# umotion_2_v1_2_pcb_2.net
KiCad netlist of a schematic drawn in EAGLE
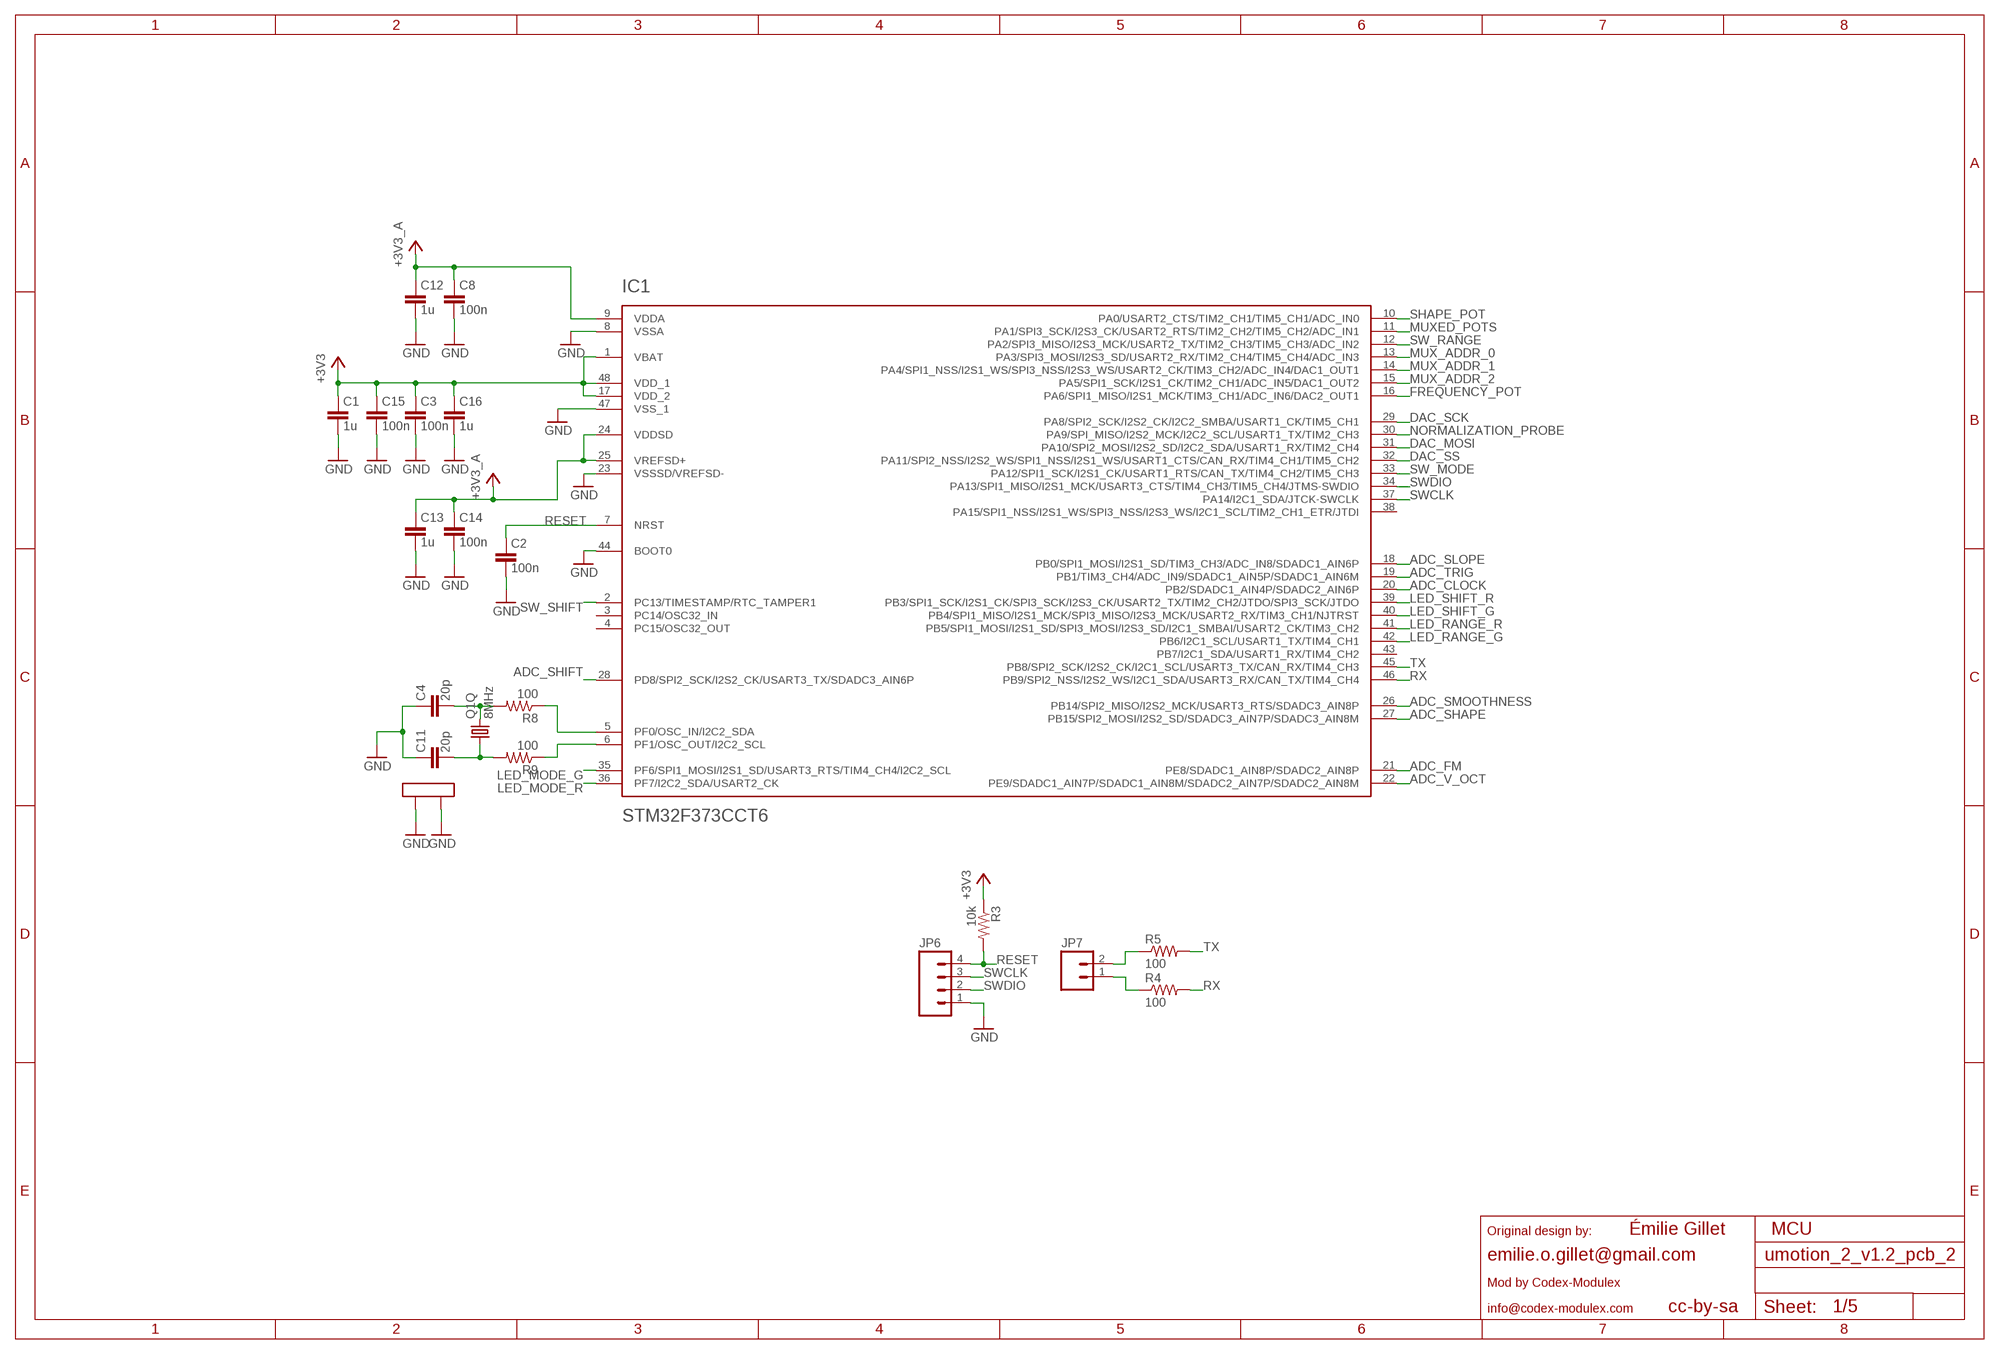
[diagram p0: schematic, sheet 1]
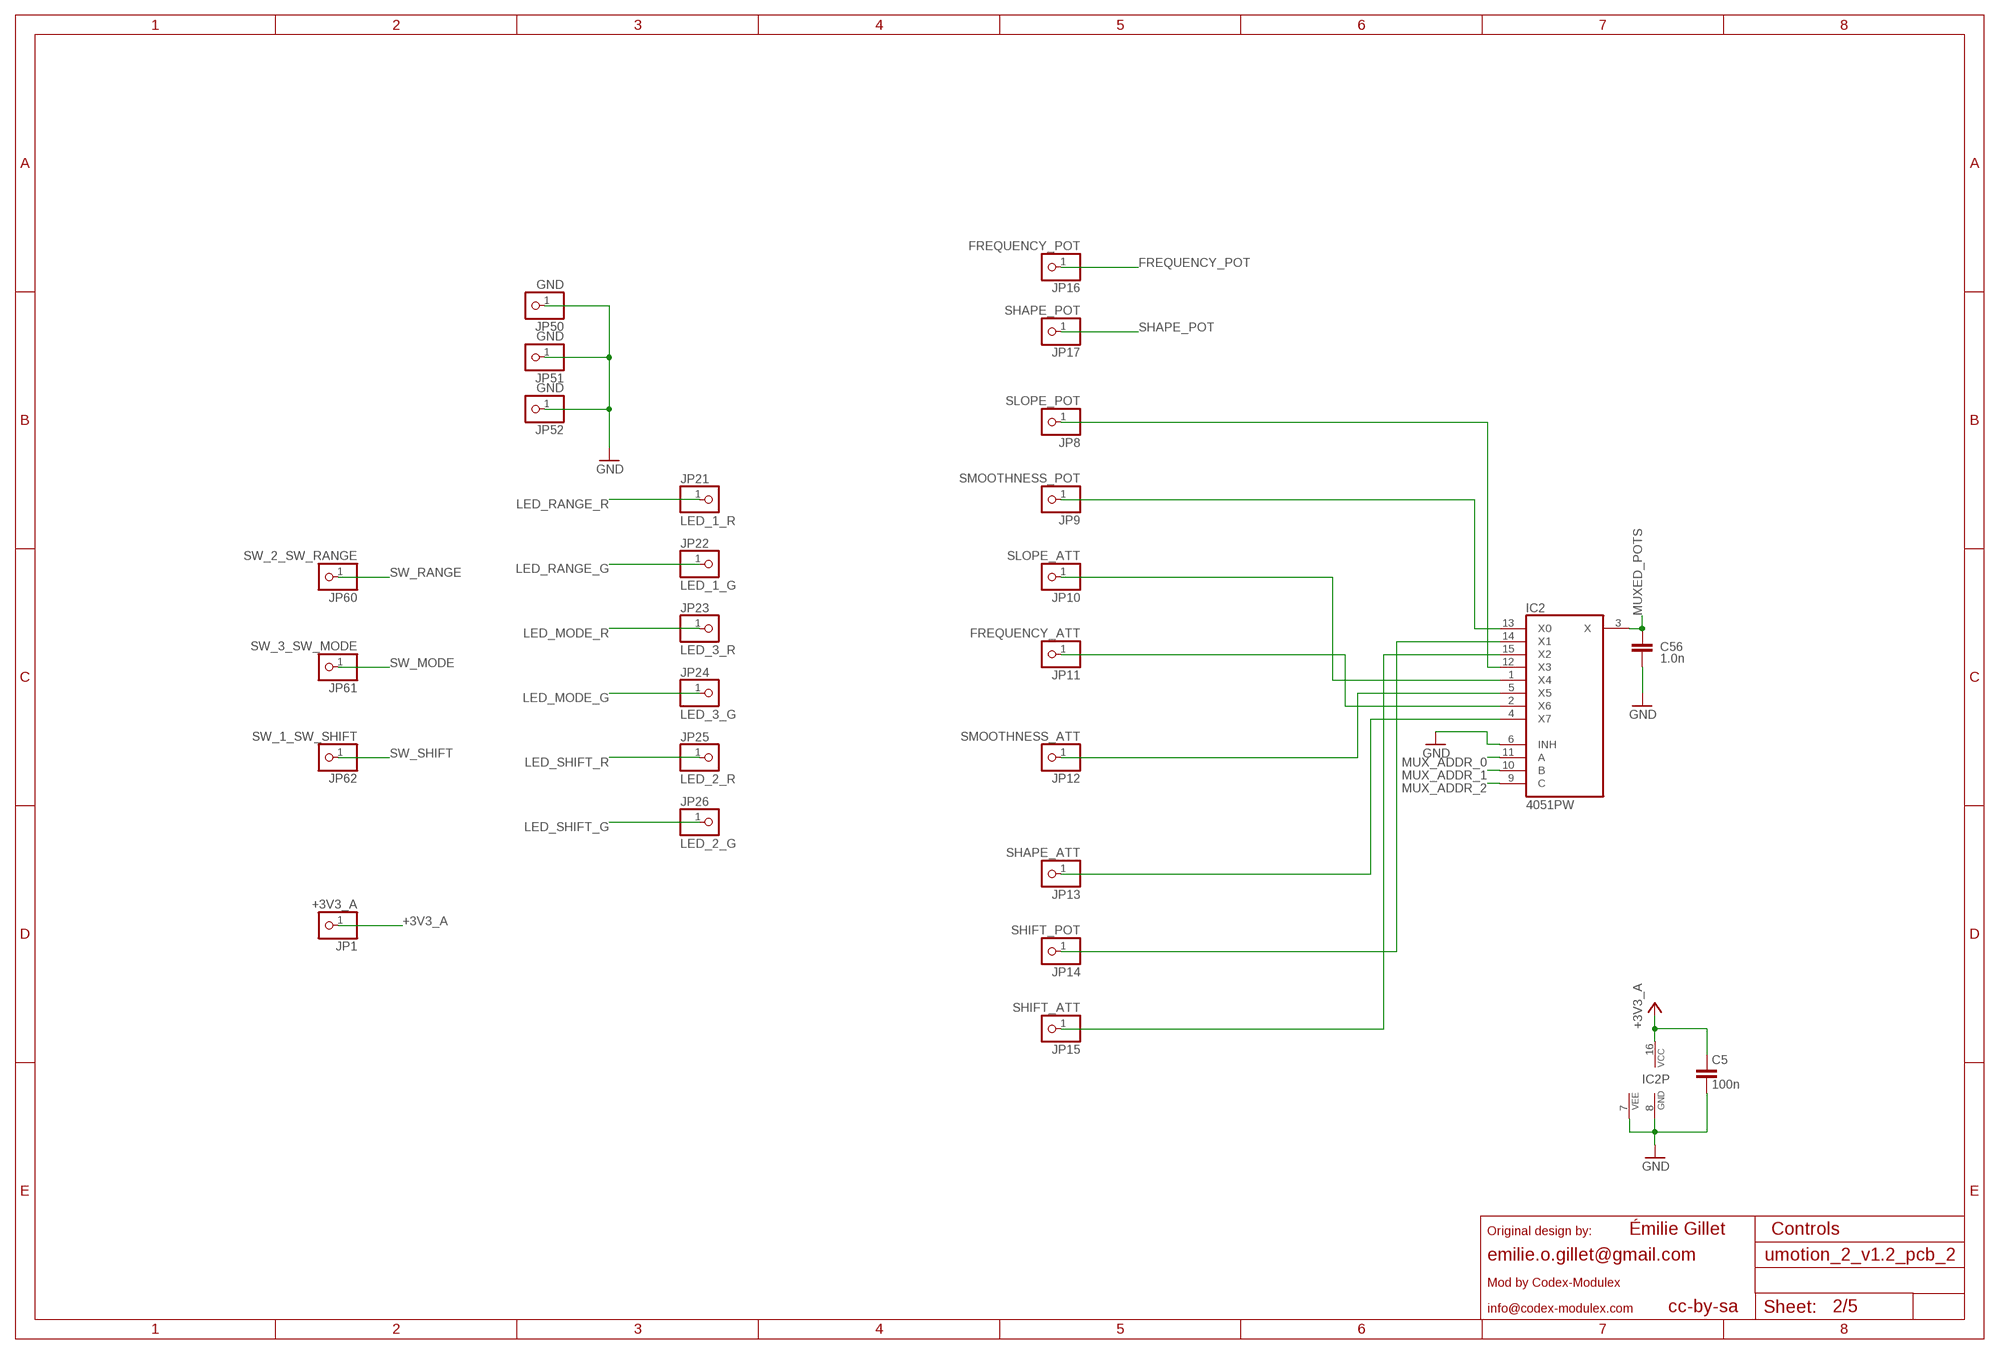
[diagram p1: schematic, sheet 2]
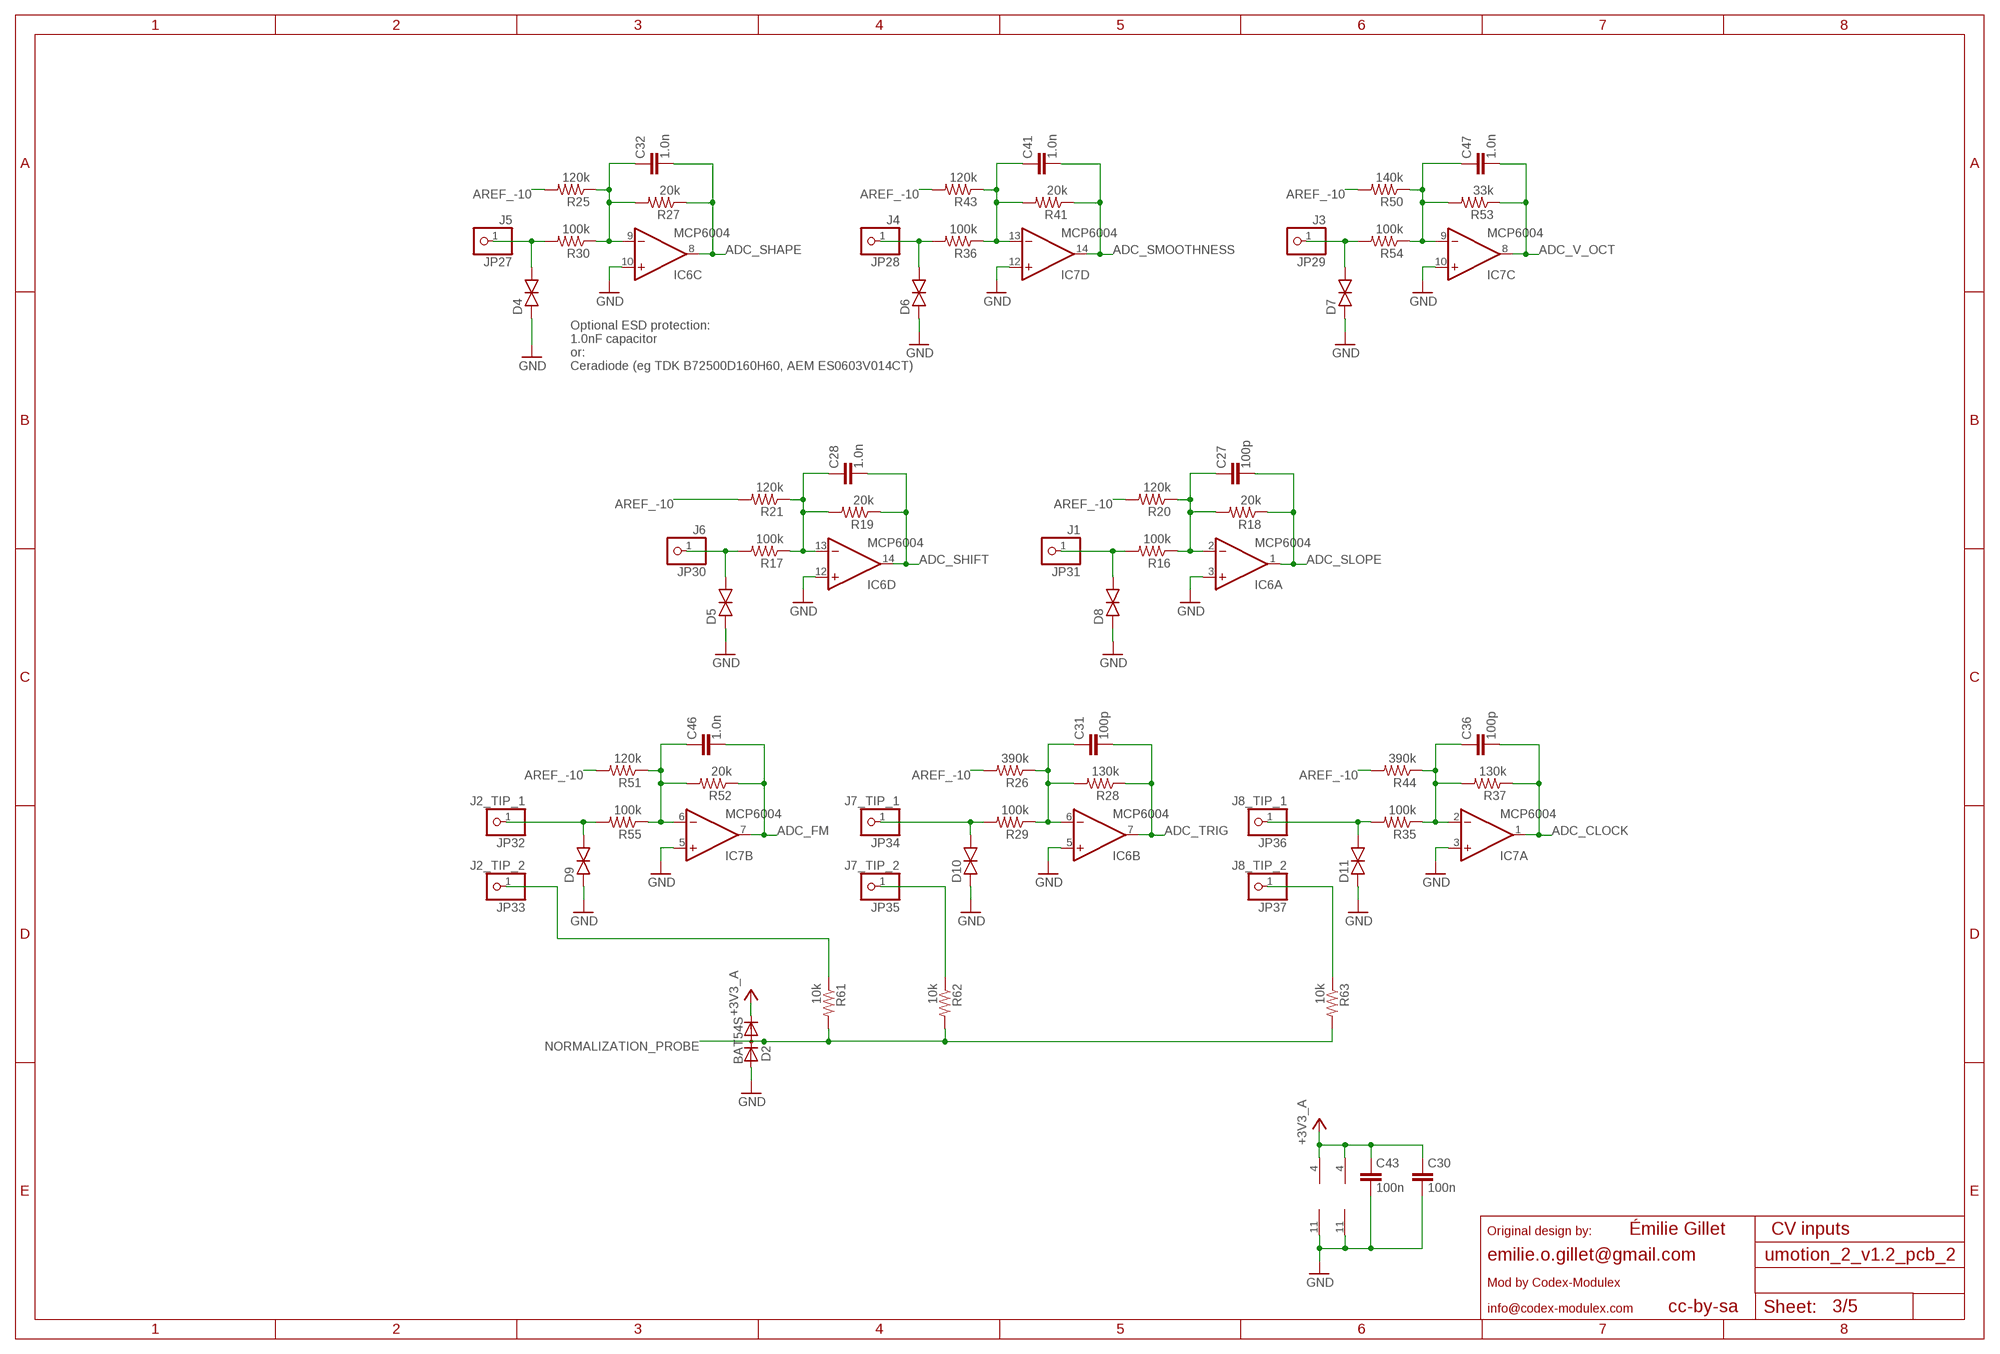
[diagram p2: schematic, sheet 3]
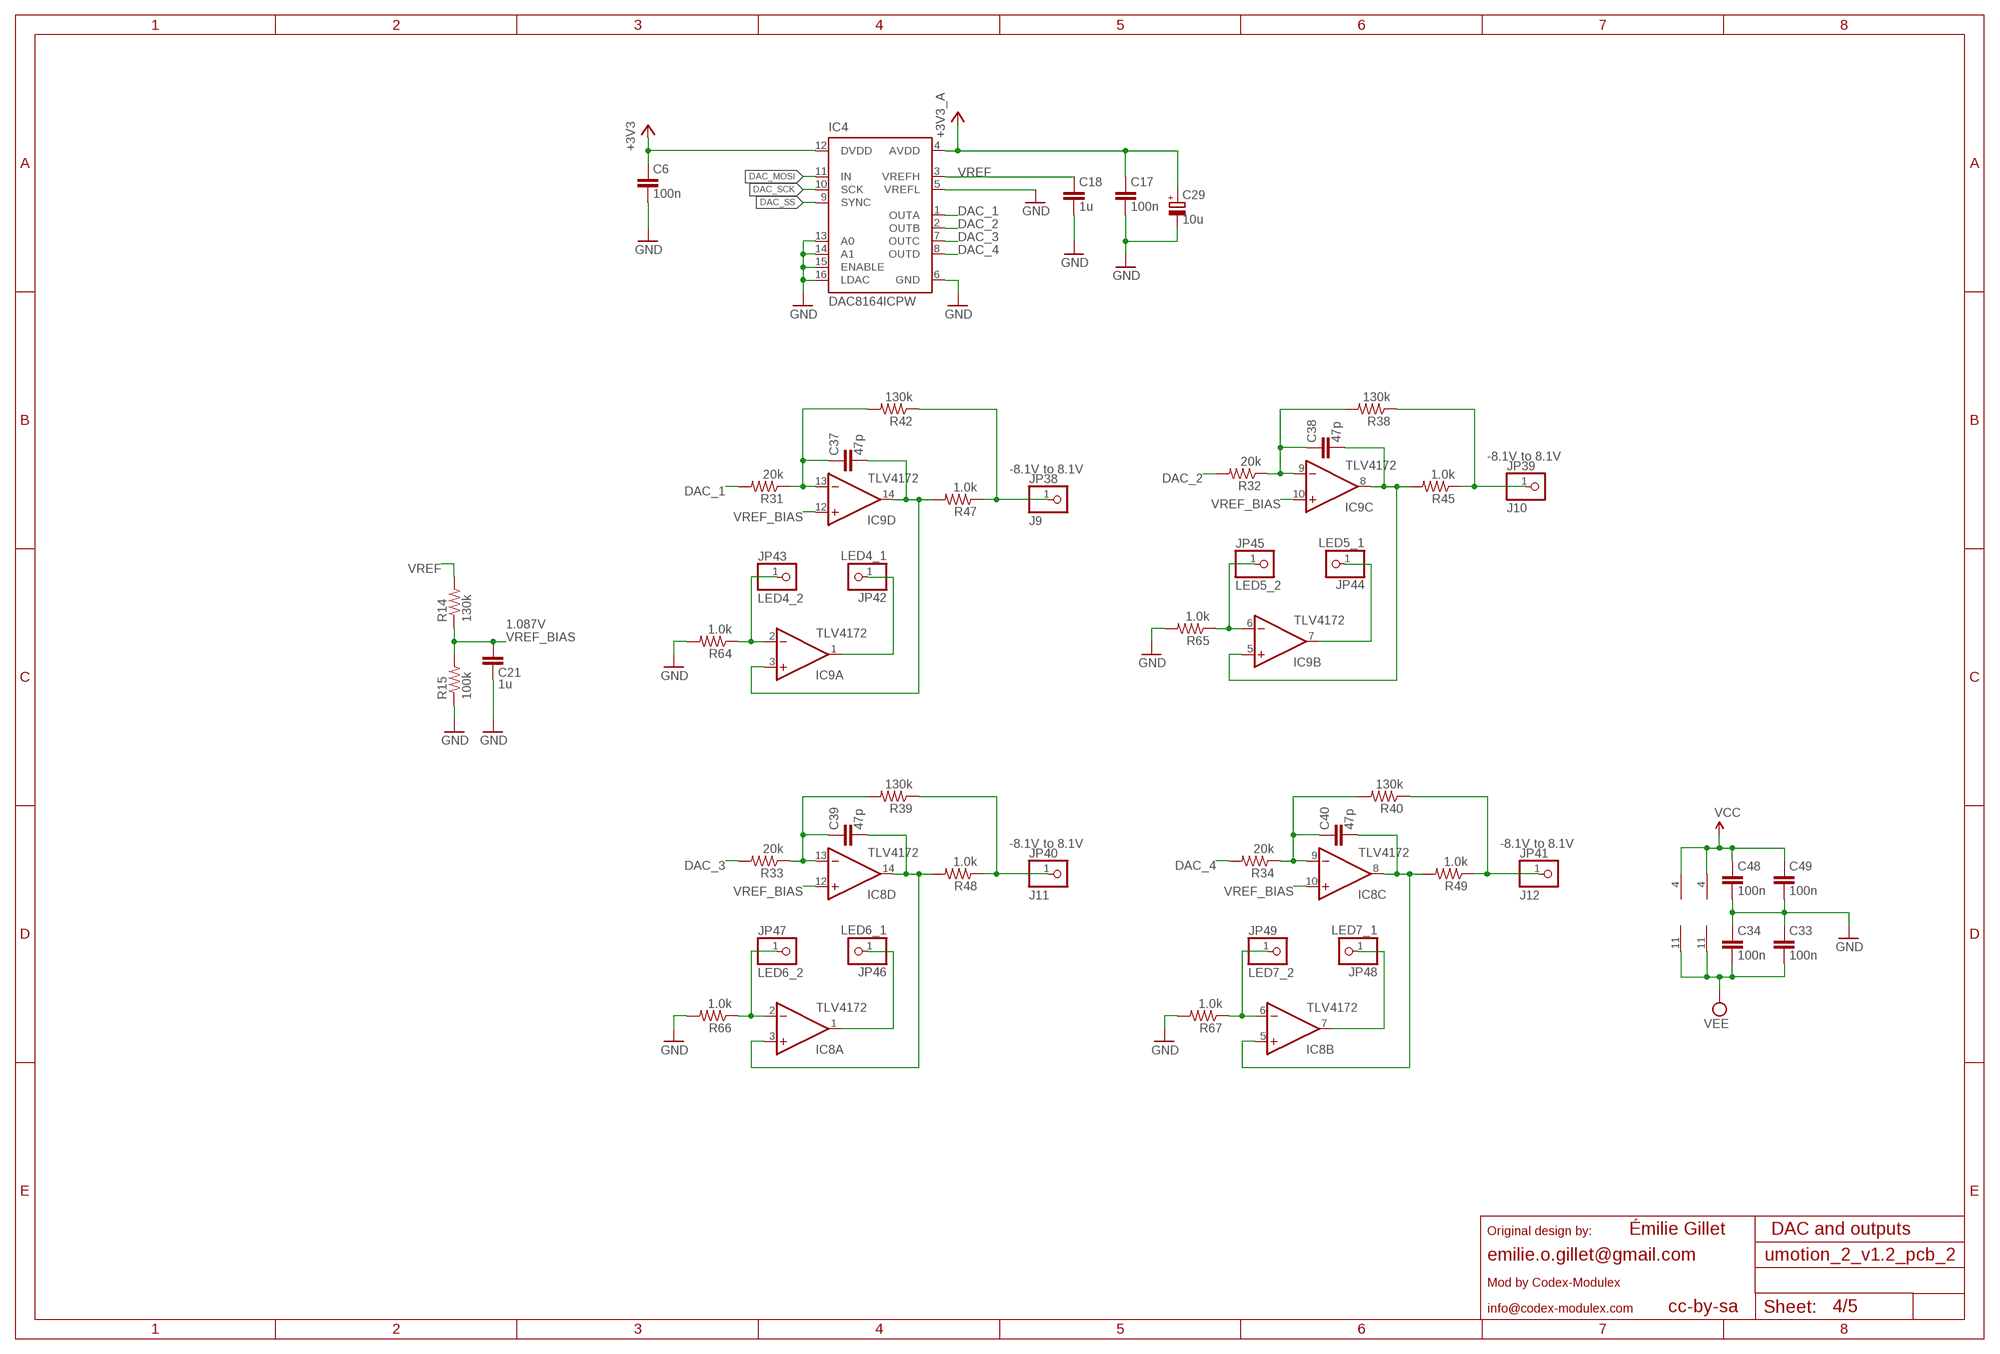
[diagram p3: schematic, sheet 4]
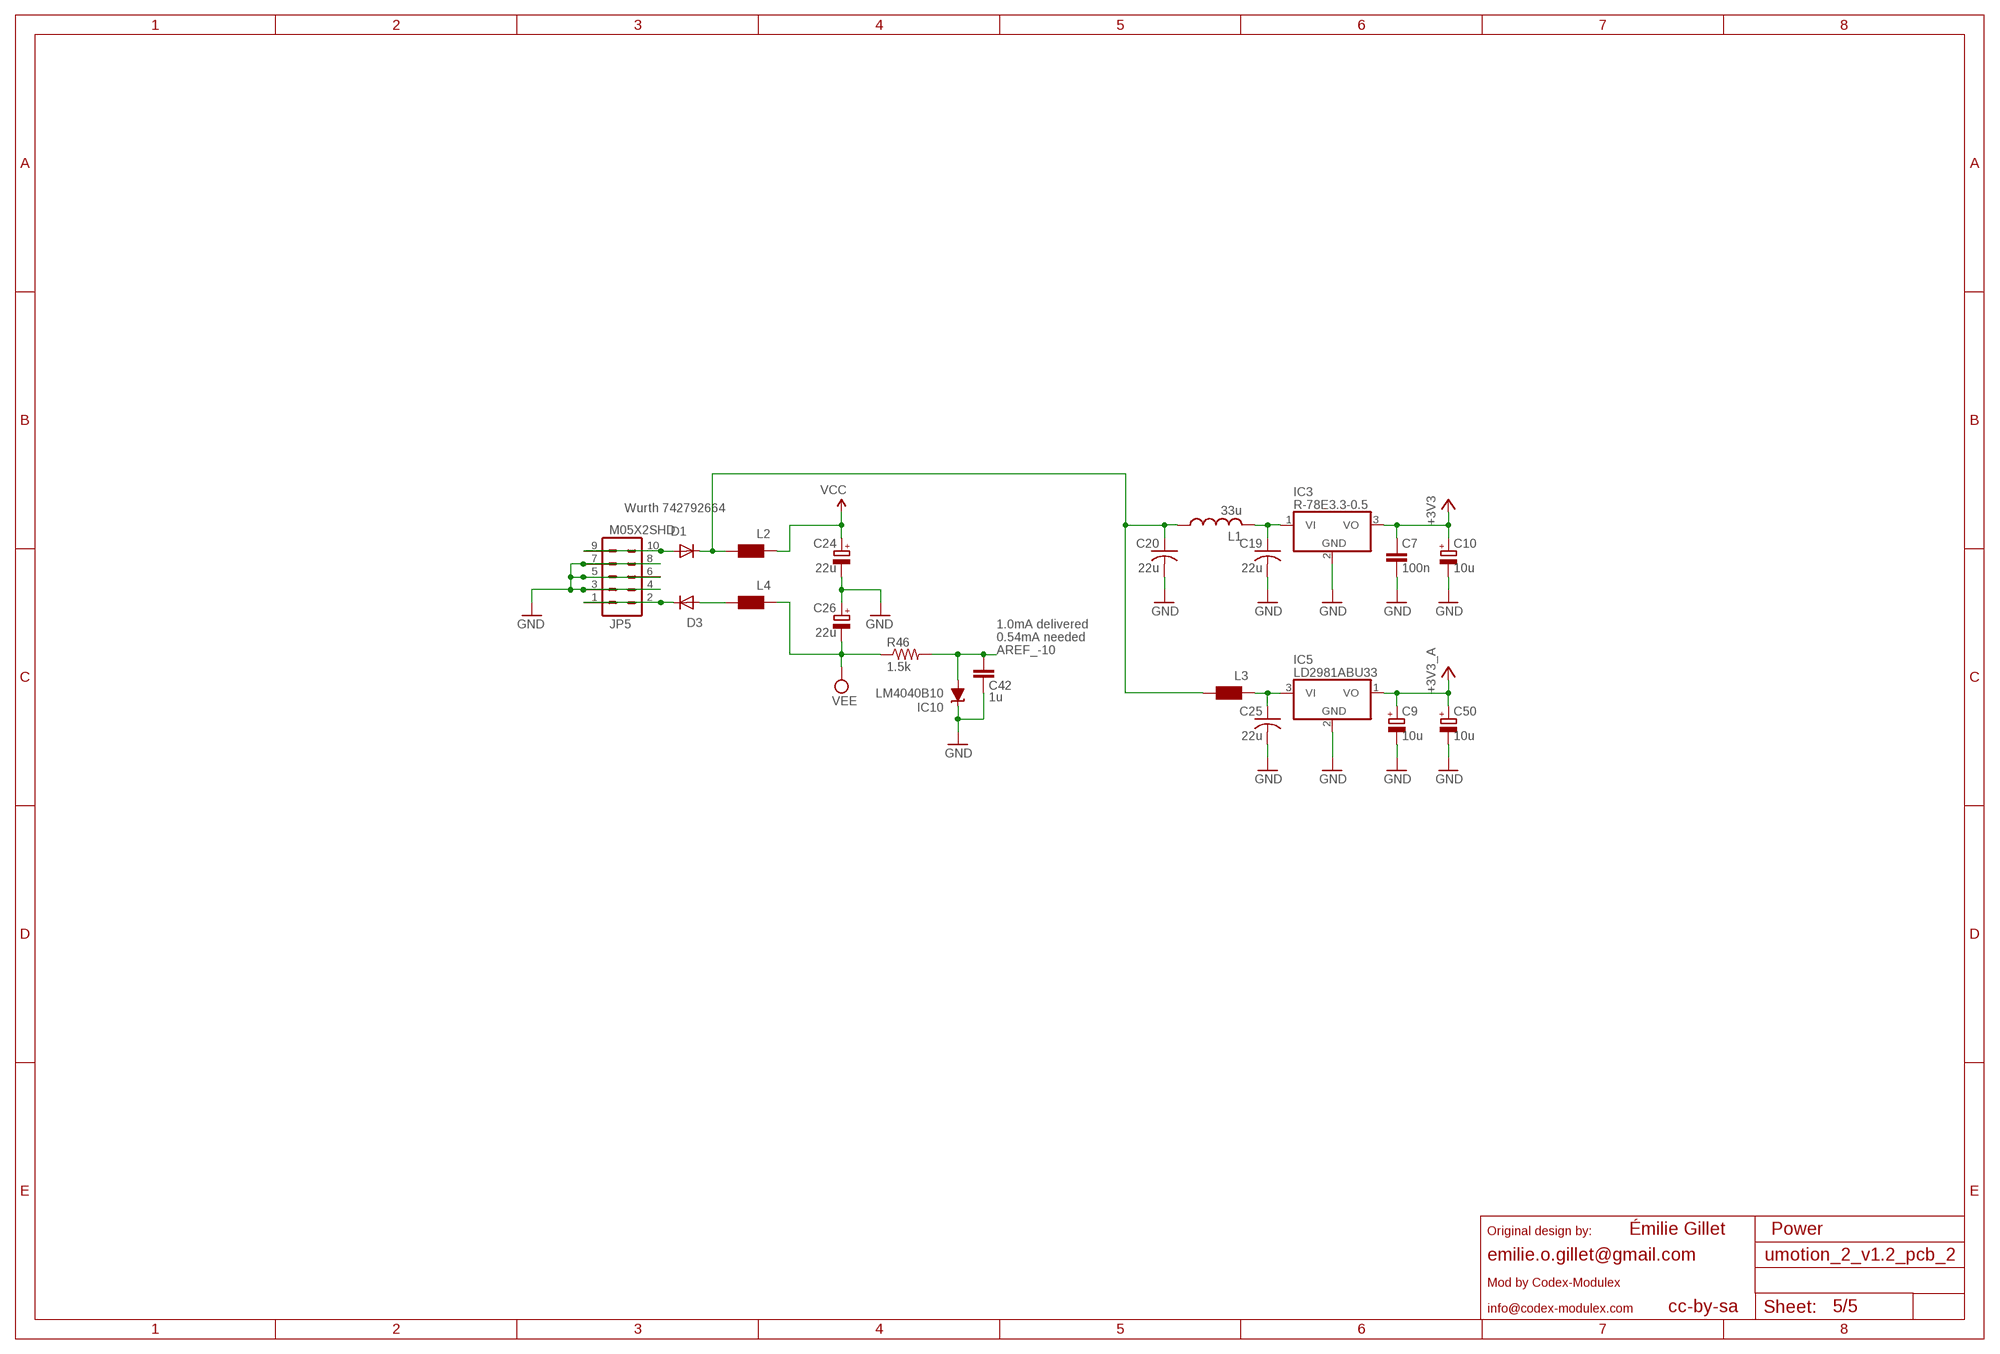
[diagram p4: schematic, sheet 5]

(export (version "E")
  (design (tool "Eeschema 10.0.6"))
  (components
    (comp (ref "C6")
      (value "100n")
      (footprint "eagle-import:PARTS_AMAN_RESISTOR_0603")
      (libsource (lib "eagle-import") (part "PARTS_AMAN_CAPACITOR"))
    )
    (comp (ref "C17")
      (value "100n")
      (footprint "eagle-import:PARTS_AMAN_RESISTOR_0603")
      (libsource (lib "eagle-import") (part "PARTS_AMAN_CAPACITOR"))
    )
    (comp (ref "C18")
      (value "1u")
      (footprint "eagle-import:PARTS_AMAN_RESISTOR_0603")
      (libsource (lib "eagle-import") (part "PARTS_AMAN_CAPACITOR"))
    )
    (comp (ref "C21")
      (value "1u")
      (footprint "eagle-import:PARTS_AMAN_RESISTOR_0603")
      (libsource (lib "eagle-import") (part "PARTS_AMAN_CAPACITOR"))
    )
    (comp (ref "C29")
      (value "10u")
      (footprint "eagle-import:PANASONIC_B")
      (libsource (lib "eagle-import") (part "CPOL-EUB"))
    )
    (comp (ref "C33")
      (value "100n")
      (footprint "eagle-import:PARTS_AMAN_RESISTOR_0603")
      (libsource (lib "eagle-import") (part "PARTS_AMAN_CAPACITOR"))
    )
    (comp (ref "C34")
      (value "100n")
      (footprint "eagle-import:PARTS_AMAN_RESISTOR_0603")
      (libsource (lib "eagle-import") (part "PARTS_AMAN_CAPACITOR"))
    )
    (comp (ref "C37")
      (value "47p")
      (footprint "eagle-import:PARTS_AMAN_RESISTOR_0603")
      (libsource (lib "eagle-import") (part "PARTS_AMAN_CAPACITOR"))
    )
    (comp (ref "C38")
      (value "47p")
      (footprint "eagle-import:PARTS_AMAN_RESISTOR_0603")
      (libsource (lib "eagle-import") (part "PARTS_AMAN_CAPACITOR"))
    )
    (comp (ref "C39")
      (value "47p")
      (footprint "eagle-import:PARTS_AMAN_RESISTOR_0603")
      (libsource (lib "eagle-import") (part "PARTS_AMAN_CAPACITOR"))
    )
    (comp (ref "C40")
      (value "47p")
      (footprint "eagle-import:PARTS_AMAN_RESISTOR_0603")
      (libsource (lib "eagle-import") (part "PARTS_AMAN_CAPACITOR"))
    )
    (comp (ref "C48")
      (value "100n")
      (footprint "eagle-import:PARTS_AMAN_RESISTOR_0603")
      (libsource (lib "eagle-import") (part "PARTS_AMAN_CAPACITOR"))
    )
    (comp (ref "C49")
      (value "100n")
      (footprint "eagle-import:PARTS_AMAN_RESISTOR_0603")
      (libsource (lib "eagle-import") (part "PARTS_AMAN_CAPACITOR"))
    )
    (comp (ref "IC4")
      (value "DAC8164ICPW")
      (footprint "eagle-import:SOP65P640X110-16N")
      (libsource (lib "eagle-import") (part "DAC8564"))
    )
    (comp (ref "IC8")
      (value "TLV4172")
      (footprint "eagle-import:TSSOP14_065")
      (libsource (lib "eagle-import") (part "TL074PW"))
    )
    (comp (ref "IC9")
      (value "TLV4172")
      (footprint "eagle-import:TSSOP14_065")
      (libsource (lib "eagle-import") (part "TL074PW"))
    )
    (comp (ref "JP38")
      (value "J9")
      (footprint "eagle-import:PARTS_AMAN_1X01")
      (libsource (lib "eagle-import") (part "PARTS_AMAN_PINHD-1X1"))
    )
    (comp (ref "JP39")
      (value "J10")
      (footprint "eagle-import:PARTS_AMAN_1X01")
      (libsource (lib "eagle-import") (part "PARTS_AMAN_PINHD-1X1"))
    )
    (comp (ref "JP40")
      (value "J11")
      (footprint "eagle-import:PARTS_AMAN_1X01")
      (libsource (lib "eagle-import") (part "PARTS_AMAN_PINHD-1X1"))
    )
    (comp (ref "JP41")
      (value "J12")
      (footprint "eagle-import:PARTS_AMAN_1X01")
      (libsource (lib "eagle-import") (part "PARTS_AMAN_PINHD-1X1"))
    )
    (comp (ref "JP42")
      (value "LED4_1")
      (footprint "eagle-import:PARTS_AMAN_1X01")
      (libsource (lib "eagle-import") (part "PARTS_AMAN_PINHD-1X1"))
    )
    (comp (ref "JP43")
      (value "LED4_2")
      (footprint "eagle-import:PARTS_AMAN_1X01")
      (libsource (lib "eagle-import") (part "PARTS_AMAN_PINHD-1X1"))
    )
    (comp (ref "JP44")
      (value "LED5_1")
      (footprint "eagle-import:PARTS_AMAN_1X01")
      (libsource (lib "eagle-import") (part "PARTS_AMAN_PINHD-1X1"))
    )
    (comp (ref "JP45")
      (value "LED5_2")
      (footprint "eagle-import:PARTS_AMAN_1X01")
      (libsource (lib "eagle-import") (part "PARTS_AMAN_PINHD-1X1"))
    )
    (comp (ref "JP46")
      (value "LED6_1")
      (footprint "eagle-import:PARTS_AMAN_1X01")
      (libsource (lib "eagle-import") (part "PARTS_AMAN_PINHD-1X1"))
    )
    (comp (ref "JP47")
      (value "LED6_2")
      (footprint "eagle-import:PARTS_AMAN_1X01")
      (libsource (lib "eagle-import") (part "PARTS_AMAN_PINHD-1X1"))
    )
    (comp (ref "JP48")
      (value "LED7_1")
      (footprint "eagle-import:PARTS_AMAN_1X01")
      (libsource (lib "eagle-import") (part "PARTS_AMAN_PINHD-1X1"))
    )
    (comp (ref "JP49")
      (value "LED7_2")
      (footprint "eagle-import:PARTS_AMAN_1X01")
      (libsource (lib "eagle-import") (part "PARTS_AMAN_PINHD-1X1"))
    )
    (comp (ref "R14")
      (value "130k")
      (footprint "eagle-import:PARTS_AMAN_RESISTOR_0603")
      (libsource (lib "eagle-import") (part "PARTS_AMAN_RESISTOR"))
    )
    (comp (ref "R15")
      (value "100k")
      (footprint "eagle-import:PARTS_AMAN_RESISTOR_0603")
      (libsource (lib "eagle-import") (part "PARTS_AMAN_RESISTOR"))
    )
    (comp (ref "R31")
      (value "20k")
      (footprint "eagle-import:PARTS_AMAN_RESISTOR_0603")
      (libsource (lib "eagle-import") (part "PARTS_AMAN_RESISTOR"))
    )
    (comp (ref "R32")
      (value "20k")
      (footprint "eagle-import:PARTS_AMAN_RESISTOR_0603")
      (libsource (lib "eagle-import") (part "PARTS_AMAN_RESISTOR"))
    )
    (comp (ref "R33")
      (value "20k")
      (footprint "eagle-import:PARTS_AMAN_RESISTOR_0603")
      (libsource (lib "eagle-import") (part "PARTS_AMAN_RESISTOR"))
    )
    (comp (ref "R34")
      (value "20k")
      (footprint "eagle-import:PARTS_AMAN_RESISTOR_0603")
      (libsource (lib "eagle-import") (part "PARTS_AMAN_RESISTOR"))
    )
    (comp (ref "R38")
      (value "130k")
      (footprint "eagle-import:PARTS_AMAN_RESISTOR_0603")
      (libsource (lib "eagle-import") (part "PARTS_AMAN_RESISTOR"))
    )
    (comp (ref "R39")
      (value "130k")
      (footprint "eagle-import:PARTS_AMAN_RESISTOR_0603")
      (libsource (lib "eagle-import") (part "PARTS_AMAN_RESISTOR"))
    )
    (comp (ref "R40")
      (value "130k")
      (footprint "eagle-import:PARTS_AMAN_RESISTOR_0603")
      (libsource (lib "eagle-import") (part "PARTS_AMAN_RESISTOR"))
    )
    (comp (ref "R42")
      (value "130k")
      (footprint "eagle-import:PARTS_AMAN_RESISTOR_0603")
      (libsource (lib "eagle-import") (part "PARTS_AMAN_RESISTOR"))
    )
    (comp (ref "R45")
      (value "1.0k")
      (footprint "eagle-import:R0603")
      (libsource (lib "eagle-import") (part "R-US_R0603"))
    )
    (comp (ref "R47")
      (value "1.0k")
      (footprint "eagle-import:R0603")
      (libsource (lib "eagle-import") (part "R-US_R0603"))
    )
    (comp (ref "R48")
      (value "1.0k")
      (footprint "eagle-import:R0603")
      (libsource (lib "eagle-import") (part "R-US_R0603"))
    )
    (comp (ref "R49")
      (value "1.0k")
      (footprint "eagle-import:R0603")
      (libsource (lib "eagle-import") (part "R-US_R0603"))
    )
    (comp (ref "R64")
      (value "1.0k")
      (footprint "eagle-import:PARTS_AMAN_RESISTOR_0603")
      (libsource (lib "eagle-import") (part "PARTS_AMAN_RESISTOR"))
    )
    (comp (ref "R65")
      (value "1.0k")
      (footprint "eagle-import:PARTS_AMAN_RESISTOR_0603")
      (libsource (lib "eagle-import") (part "PARTS_AMAN_RESISTOR"))
    )
    (comp (ref "R66")
      (value "1.0k")
      (footprint "eagle-import:PARTS_AMAN_RESISTOR_0603")
      (libsource (lib "eagle-import") (part "PARTS_AMAN_RESISTOR"))
    )
    (comp (ref "R67")
      (value "1.0k")
      (footprint "eagle-import:PARTS_AMAN_RESISTOR_0603")
      (libsource (lib "eagle-import") (part "PARTS_AMAN_RESISTOR"))
    )
    (comp (ref "C5")
      (value "100n")
      (footprint "eagle-import:PARTS_AMAN_RESISTOR_0603")
      (libsource (lib "eagle-import") (part "PARTS_AMAN_CAPACITOR"))
    )
    (comp (ref "C56")
      (value "1.0n")
      (footprint "eagle-import:PARTS_AMAN_RESISTOR_0603")
      (libsource (lib "eagle-import") (part "PARTS_AMAN_CAPACITOR"))
    )
    (comp (ref "IC2")
      (value "4051PW")
      (footprint "eagle-import:TSSOP16_065")
      (libsource (lib "eagle-import") (part "4051PW"))
    )
    (comp (ref "JP1")
      (value "+3V3_A")
      (footprint "eagle-import:PARTS_AMAN_1X01")
      (libsource (lib "eagle-import") (part "PARTS_AMAN_PINHD-1X1"))
    )
    (comp (ref "JP8")
      (value "SLOPE_POT")
      (footprint "eagle-import:PARTS_AMAN_1X01")
      (libsource (lib "eagle-import") (part "PARTS_AMAN_PINHD-1X1"))
    )
    (comp (ref "JP9")
      (value "SMOOTHNESS_POT")
      (footprint "eagle-import:PARTS_AMAN_1X01")
      (libsource (lib "eagle-import") (part "PARTS_AMAN_PINHD-1X1"))
    )
    (comp (ref "JP10")
      (value "SLOPE_ATT")
      (footprint "eagle-import:PARTS_AMAN_1X01")
      (libsource (lib "eagle-import") (part "PARTS_AMAN_PINHD-1X1"))
    )
    (comp (ref "JP11")
      (value "FREQUENCY_ATT")
      (footprint "eagle-import:PARTS_AMAN_1X01")
      (libsource (lib "eagle-import") (part "PARTS_AMAN_PINHD-1X1"))
    )
    (comp (ref "JP12")
      (value "SMOOTHNESS_ATT")
      (footprint "eagle-import:PARTS_AMAN_1X01")
      (libsource (lib "eagle-import") (part "PARTS_AMAN_PINHD-1X1"))
    )
    (comp (ref "JP13")
      (value "SHAPE_ATT")
      (footprint "eagle-import:PARTS_AMAN_1X01")
      (libsource (lib "eagle-import") (part "PARTS_AMAN_PINHD-1X1"))
    )
    (comp (ref "JP14")
      (value "SHIFT_POT")
      (footprint "eagle-import:PARTS_AMAN_1X01")
      (libsource (lib "eagle-import") (part "PARTS_AMAN_PINHD-1X1"))
    )
    (comp (ref "JP15")
      (value "SHIFT_ATT")
      (footprint "eagle-import:PARTS_AMAN_1X01")
      (libsource (lib "eagle-import") (part "PARTS_AMAN_PINHD-1X1"))
    )
    (comp (ref "JP16")
      (value "FREQUENCY_POT")
      (footprint "eagle-import:PARTS_AMAN_1X01")
      (libsource (lib "eagle-import") (part "PARTS_AMAN_PINHD-1X1"))
    )
    (comp (ref "JP17")
      (value "SHAPE_POT")
      (footprint "eagle-import:PARTS_AMAN_1X01")
      (libsource (lib "eagle-import") (part "PARTS_AMAN_PINHD-1X1"))
    )
    (comp (ref "JP21")
      (value "LED_1_R")
      (footprint "eagle-import:PARTS_AMAN_1X01")
      (libsource (lib "eagle-import") (part "PARTS_AMAN_PINHD-1X1"))
    )
    (comp (ref "JP22")
      (value "LED_1_G")
      (footprint "eagle-import:PARTS_AMAN_1X01")
      (libsource (lib "eagle-import") (part "PARTS_AMAN_PINHD-1X1"))
    )
    (comp (ref "JP23")
      (value "LED_3_R")
      (footprint "eagle-import:PARTS_AMAN_1X01")
      (libsource (lib "eagle-import") (part "PARTS_AMAN_PINHD-1X1"))
    )
    (comp (ref "JP24")
      (value "LED_3_G")
      (footprint "eagle-import:PARTS_AMAN_1X01")
      (libsource (lib "eagle-import") (part "PARTS_AMAN_PINHD-1X1"))
    )
    (comp (ref "JP25")
      (value "LED_2_R")
      (footprint "eagle-import:PARTS_AMAN_1X01")
      (libsource (lib "eagle-import") (part "PARTS_AMAN_PINHD-1X1"))
    )
    (comp (ref "JP26")
      (value "LED_2_G")
      (footprint "eagle-import:PARTS_AMAN_1X01")
      (libsource (lib "eagle-import") (part "PARTS_AMAN_PINHD-1X1"))
    )
    (comp (ref "JP50")
      (value "GND")
      (footprint "eagle-import:PARTS_AMAN_1X01")
      (libsource (lib "eagle-import") (part "PARTS_AMAN_PINHD-1X1"))
    )
    (comp (ref "JP51")
      (value "GND")
      (footprint "eagle-import:PARTS_AMAN_1X01")
      (libsource (lib "eagle-import") (part "PARTS_AMAN_PINHD-1X1"))
    )
    (comp (ref "JP52")
      (value "GND")
      (footprint "eagle-import:PARTS_AMAN_1X01")
      (libsource (lib "eagle-import") (part "PARTS_AMAN_PINHD-1X1"))
    )
    (comp (ref "JP60")
      (value "SW_2_SW_RANGE")
      (footprint "eagle-import:PARTS_AMAN_1X01")
      (libsource (lib "eagle-import") (part "PARTS_AMAN_PINHD-1X1"))
    )
    (comp (ref "JP61")
      (value "SW_3_SW_MODE")
      (footprint "eagle-import:PARTS_AMAN_1X01")
      (libsource (lib "eagle-import") (part "PARTS_AMAN_PINHD-1X1"))
    )
    (comp (ref "JP62")
      (value "SW_1_SW_SHIFT")
      (footprint "eagle-import:PARTS_AMAN_1X01")
      (libsource (lib "eagle-import") (part "PARTS_AMAN_PINHD-1X1"))
    )
    (comp (ref "C1")
      (value "1u")
      (footprint "eagle-import:PARTS_AMAN_RESISTOR_0603")
      (libsource (lib "eagle-import") (part "PARTS_AMAN_CAPACITOR"))
    )
    (comp (ref "C2")
      (value "100n")
      (footprint "eagle-import:PARTS_AMAN_RESISTOR_0603")
      (libsource (lib "eagle-import") (part "PARTS_AMAN_CAPACITOR"))
    )
    (comp (ref "C3")
      (value "100n")
      (footprint "eagle-import:PARTS_AMAN_RESISTOR_0603")
      (libsource (lib "eagle-import") (part "PARTS_AMAN_CAPACITOR"))
    )
    (comp (ref "C4")
      (value "20p")
      (footprint "eagle-import:PARTS_AMAN_RESISTOR_0603")
      (libsource (lib "eagle-import") (part "PARTS_AMAN_CAPACITOR"))
    )
    (comp (ref "C8")
      (value "100n")
      (footprint "eagle-import:PARTS_AMAN_RESISTOR_0603")
      (libsource (lib "eagle-import") (part "PARTS_AMAN_CAPACITOR"))
    )
    (comp (ref "C11")
      (value "20p")
      (footprint "eagle-import:PARTS_AMAN_RESISTOR_0603")
      (libsource (lib "eagle-import") (part "PARTS_AMAN_CAPACITOR"))
    )
    (comp (ref "C12")
      (value "1u")
      (footprint "eagle-import:PARTS_AMAN_RESISTOR_0603")
      (libsource (lib "eagle-import") (part "PARTS_AMAN_CAPACITOR"))
    )
    (comp (ref "C13")
      (value "1u")
      (footprint "eagle-import:PARTS_AMAN_RESISTOR_0603")
      (libsource (lib "eagle-import") (part "PARTS_AMAN_CAPACITOR"))
    )
    (comp (ref "C14")
      (value "100n")
      (footprint "eagle-import:PARTS_AMAN_RESISTOR_0603")
      (libsource (lib "eagle-import") (part "PARTS_AMAN_CAPACITOR"))
    )
    (comp (ref "C15")
      (value "100n")
      (footprint "eagle-import:PARTS_AMAN_RESISTOR_0603")
      (libsource (lib "eagle-import") (part "PARTS_AMAN_CAPACITOR"))
    )
    (comp (ref "C16")
      (value "1u")
      (footprint "eagle-import:PARTS_AMAN_RESISTOR_0603")
      (libsource (lib "eagle-import") (part "PARTS_AMAN_CAPACITOR"))
    )
    (comp (ref "IC1")
      (value "STM32F373CCT6")
      (footprint "eagle-import:LQFP48")
      (libsource (lib "eagle-import") (part "STM32F373C"))
    )
    (comp (ref "JP6")
      (value "M04PTH")
      (footprint "eagle-import:1X04")
      (libsource (lib "eagle-import") (part "M04PTH"))
    )
    (comp (ref "JP7")
      (value "M02PTH")
      (footprint "eagle-import:1X02")
      (libsource (lib "eagle-import") (part "M02PTH"))
    )
    (comp (ref "Q1")
      (value "8MHz")
      (footprint "eagle-import:CTS406")
      (libsource (lib "eagle-import") (part "CRYSTAL"))
    )
    (comp (ref "R3")
      (value "10k")
      (footprint "eagle-import:PARTS_AMAN_RESISTOR_0603")
      (libsource (lib "eagle-import") (part "PARTS_AMAN_RESISTOR"))
    )
    (comp (ref "R4")
      (value "100")
      (footprint "eagle-import:PARTS_AMAN_RESISTOR_0603")
      (libsource (lib "eagle-import") (part "PARTS_AMAN_RESISTOR"))
    )
    (comp (ref "R5")
      (value "100")
      (footprint "eagle-import:PARTS_AMAN_RESISTOR_0603")
      (libsource (lib "eagle-import") (part "PARTS_AMAN_RESISTOR"))
    )
    (comp (ref "R8")
      (value "100")
      (footprint "eagle-import:PARTS_AMAN_RESISTOR_0603")
      (libsource (lib "eagle-import") (part "PARTS_AMAN_RESISTOR"))
    )
    (comp (ref "R9")
      (value "100")
      (footprint "eagle-import:PARTS_AMAN_RESISTOR_0603")
      (libsource (lib "eagle-import") (part "PARTS_AMAN_RESISTOR"))
    )
    (comp (ref "C27")
      (value "100p")
      (footprint "eagle-import:PARTS_AMAN_RESISTOR_0603")
      (libsource (lib "eagle-import") (part "PARTS_AMAN_CAPACITOR"))
    )
    (comp (ref "C28")
      (value "1.0n")
      (footprint "eagle-import:PARTS_AMAN_RESISTOR_0603")
      (libsource (lib "eagle-import") (part "PARTS_AMAN_CAPACITOR"))
    )
    (comp (ref "C30")
      (value "100n")
      (footprint "eagle-import:PARTS_AMAN_RESISTOR_0603")
      (libsource (lib "eagle-import") (part "PARTS_AMAN_CAPACITOR"))
    )
    (comp (ref "C31")
      (value "100p")
      (footprint "eagle-import:PARTS_AMAN_RESISTOR_0603")
      (libsource (lib "eagle-import") (part "PARTS_AMAN_CAPACITOR"))
    )
    (comp (ref "C32")
      (value "1.0n")
      (footprint "eagle-import:PARTS_AMAN_RESISTOR_0603")
      (libsource (lib "eagle-import") (part "PARTS_AMAN_CAPACITOR"))
    )
    (comp (ref "C36")
      (value "100p")
      (footprint "eagle-import:PARTS_AMAN_RESISTOR_0603")
      (libsource (lib "eagle-import") (part "PARTS_AMAN_CAPACITOR"))
    )
    (comp (ref "C41")
      (value "1.0n")
      (footprint "eagle-import:PARTS_AMAN_RESISTOR_0603")
      (libsource (lib "eagle-import") (part "PARTS_AMAN_CAPACITOR"))
    )
    (comp (ref "C43")
      (value "100n")
      (footprint "eagle-import:PARTS_AMAN_RESISTOR_0603")
      (libsource (lib "eagle-import") (part "PARTS_AMAN_CAPACITOR"))
    )
    (comp (ref "C46")
      (value "1.0n")
      (footprint "eagle-import:PARTS_AMAN_RESISTOR_0603")
      (libsource (lib "eagle-import") (part "PARTS_AMAN_CAPACITOR"))
    )
    (comp (ref "C47")
      (value "1.0n")
      (footprint "eagle-import:PARTS_AMAN_RESISTOR_0603")
      (libsource (lib "eagle-import") (part "PARTS_AMAN_CAPACITOR"))
    )
    (comp (ref "D2")
      (value "BAT54S")
      (footprint "eagle-import:SOT23")
      (libsource (lib "eagle-import") (part "DIODE_2CACA-SOT23"))
    )
    (comp (ref "D4")
      (value "TVS")
      (footprint "eagle-import:0603")
      (libsource (lib "eagle-import") (part "TVS"))
    )
    (comp (ref "D5")
      (value "TVS")
      (footprint "eagle-import:0603")
      (libsource (lib "eagle-import") (part "TVS"))
    )
    (comp (ref "D6")
      (value "TVS")
      (footprint "eagle-import:0603")
      (libsource (lib "eagle-import") (part "TVS"))
    )
    (comp (ref "D7")
      (value "TVS")
      (footprint "eagle-import:0603")
      (libsource (lib "eagle-import") (part "TVS"))
    )
    (comp (ref "D8")
      (value "TVS")
      (footprint "eagle-import:0603")
      (libsource (lib "eagle-import") (part "TVS"))
    )
    (comp (ref "D9")
      (value "TVS")
      (footprint "eagle-import:0603")
      (libsource (lib "eagle-import") (part "TVS"))
    )
    (comp (ref "D10")
      (value "TVS")
      (footprint "eagle-import:0603")
      (libsource (lib "eagle-import") (part "TVS"))
    )
    (comp (ref "D11")
      (value "TVS")
      (footprint "eagle-import:0603")
      (libsource (lib "eagle-import") (part "TVS"))
    )
    (comp (ref "IC6")
      (value "MCP6004")
      (footprint "eagle-import:TSSOP14_065")
      (libsource (lib "eagle-import") (part "TL074PW"))
    )
    (comp (ref "IC7")
      (value "MCP6004")
      (footprint "eagle-import:TSSOP14_065")
      (libsource (lib "eagle-import") (part "TL074PW"))
    )
    (comp (ref "JP27")
      (value "J5")
      (footprint "eagle-import:PARTS_AMAN_1X01")
      (libsource (lib "eagle-import") (part "PARTS_AMAN_PINHD-1X1"))
    )
    (comp (ref "JP28")
      (value "J4")
      (footprint "eagle-import:PARTS_AMAN_1X01")
      (libsource (lib "eagle-import") (part "PARTS_AMAN_PINHD-1X1"))
    )
    (comp (ref "JP29")
      (value "J3")
      (footprint "eagle-import:PARTS_AMAN_1X01")
      (libsource (lib "eagle-import") (part "PARTS_AMAN_PINHD-1X1"))
    )
    (comp (ref "JP30")
      (value "J6")
      (footprint "eagle-import:PARTS_AMAN_1X01")
      (libsource (lib "eagle-import") (part "PARTS_AMAN_PINHD-1X1"))
    )
    (comp (ref "JP31")
      (value "J1")
      (footprint "eagle-import:PARTS_AMAN_1X01")
      (libsource (lib "eagle-import") (part "PARTS_AMAN_PINHD-1X1"))
    )
    (comp (ref "JP32")
      (value "J2_TIP_1")
      (footprint "eagle-import:PARTS_AMAN_1X01")
      (libsource (lib "eagle-import") (part "PARTS_AMAN_PINHD-1X1"))
    )
    (comp (ref "JP33")
      (value "J2_TIP_2")
      (footprint "eagle-import:PARTS_AMAN_1X01")
      (libsource (lib "eagle-import") (part "PARTS_AMAN_PINHD-1X1"))
    )
    (comp (ref "JP34")
      (value "J7_TIP_1")
      (footprint "eagle-import:PARTS_AMAN_1X01")
      (libsource (lib "eagle-import") (part "PARTS_AMAN_PINHD-1X1"))
    )
    (comp (ref "JP35")
      (value "J7_TIP_2")
      (footprint "eagle-import:PARTS_AMAN_1X01")
      (libsource (lib "eagle-import") (part "PARTS_AMAN_PINHD-1X1"))
    )
    (comp (ref "JP36")
      (value "J8_TIP_1")
      (footprint "eagle-import:PARTS_AMAN_1X01")
      (libsource (lib "eagle-import") (part "PARTS_AMAN_PINHD-1X1"))
    )
    (comp (ref "JP37")
      (value "J8_TIP_2")
      (footprint "eagle-import:PARTS_AMAN_1X01")
      (libsource (lib "eagle-import") (part "PARTS_AMAN_PINHD-1X1"))
    )
    (comp (ref "R16")
      (value "100k")
      (footprint "eagle-import:PARTS_AMAN_RESISTOR_0603")
      (libsource (lib "eagle-import") (part "PARTS_AMAN_RESISTOR"))
    )
    (comp (ref "R17")
      (value "100k")
      (footprint "eagle-import:PARTS_AMAN_RESISTOR_0603")
      (libsource (lib "eagle-import") (part "PARTS_AMAN_RESISTOR"))
    )
    (comp (ref "R18")
      (value "20k")
      (footprint "eagle-import:PARTS_AMAN_RESISTOR_0603")
      (libsource (lib "eagle-import") (part "PARTS_AMAN_RESISTOR"))
    )
    (comp (ref "R19")
      (value "20k")
      (footprint "eagle-import:PARTS_AMAN_RESISTOR_0603")
      (libsource (lib "eagle-import") (part "PARTS_AMAN_RESISTOR"))
    )
    (comp (ref "R20")
      (value "120k")
      (footprint "eagle-import:PARTS_AMAN_RESISTOR_0603")
      (libsource (lib "eagle-import") (part "PARTS_AMAN_RESISTOR"))
    )
    (comp (ref "R21")
      (value "120k")
      (footprint "eagle-import:PARTS_AMAN_RESISTOR_0603")
      (libsource (lib "eagle-import") (part "PARTS_AMAN_RESISTOR"))
    )
    (comp (ref "R25")
      (value "120k")
      (footprint "eagle-import:PARTS_AMAN_RESISTOR_0603")
      (libsource (lib "eagle-import") (part "PARTS_AMAN_RESISTOR"))
    )
    (comp (ref "R26")
      (value "390k")
      (footprint "eagle-import:PARTS_AMAN_RESISTOR_0603")
      (libsource (lib "eagle-import") (part "PARTS_AMAN_RESISTOR"))
    )
    (comp (ref "R27")
      (value "20k")
      (footprint "eagle-import:PARTS_AMAN_RESISTOR_0603")
      (libsource (lib "eagle-import") (part "PARTS_AMAN_RESISTOR"))
    )
    (comp (ref "R28")
      (value "130k")
      (footprint "eagle-import:PARTS_AMAN_RESISTOR_0603")
      (libsource (lib "eagle-import") (part "PARTS_AMAN_RESISTOR"))
    )
    (comp (ref "R29")
      (value "100k")
      (footprint "eagle-import:PARTS_AMAN_RESISTOR_0603")
      (libsource (lib "eagle-import") (part "PARTS_AMAN_RESISTOR"))
    )
    (comp (ref "R30")
      (value "100k")
      (footprint "eagle-import:PARTS_AMAN_RESISTOR_0603")
      (libsource (lib "eagle-import") (part "PARTS_AMAN_RESISTOR"))
    )
    (comp (ref "R35")
      (value "100k")
      (footprint "eagle-import:PARTS_AMAN_RESISTOR_0603")
      (libsource (lib "eagle-import") (part "PARTS_AMAN_RESISTOR"))
    )
    (comp (ref "R36")
      (value "100k")
      (footprint "eagle-import:PARTS_AMAN_RESISTOR_0603")
      (libsource (lib "eagle-import") (part "PARTS_AMAN_RESISTOR"))
    )
    (comp (ref "R37")
      (value "130k")
      (footprint "eagle-import:PARTS_AMAN_RESISTOR_0603")
      (libsource (lib "eagle-import") (part "PARTS_AMAN_RESISTOR"))
    )
    (comp (ref "R41")
      (value "20k")
      (footprint "eagle-import:PARTS_AMAN_RESISTOR_0603")
      (libsource (lib "eagle-import") (part "PARTS_AMAN_RESISTOR"))
    )
    (comp (ref "R43")
      (value "120k")
      (footprint "eagle-import:PARTS_AMAN_RESISTOR_0603")
      (libsource (lib "eagle-import") (part "PARTS_AMAN_RESISTOR"))
    )
    (comp (ref "R44")
      (value "390k")
      (footprint "eagle-import:PARTS_AMAN_RESISTOR_0603")
      (libsource (lib "eagle-import") (part "PARTS_AMAN_RESISTOR"))
    )
    (comp (ref "R50")
      (value "140k")
      (footprint "eagle-import:PARTS_AMAN_RESISTOR_0603")
      (libsource (lib "eagle-import") (part "PARTS_AMAN_RESISTOR"))
    )
    (comp (ref "R51")
      (value "120k")
      (footprint "eagle-import:PARTS_AMAN_RESISTOR_0603")
      (libsource (lib "eagle-import") (part "PARTS_AMAN_RESISTOR"))
    )
    (comp (ref "R52")
      (value "20k")
      (footprint "eagle-import:PARTS_AMAN_RESISTOR_0603")
      (libsource (lib "eagle-import") (part "PARTS_AMAN_RESISTOR"))
    )
    (comp (ref "R53")
      (value "33k")
      (footprint "eagle-import:PARTS_AMAN_RESISTOR_0603")
      (libsource (lib "eagle-import") (part "PARTS_AMAN_RESISTOR"))
    )
    (comp (ref "R54")
      (value "100k")
      (footprint "eagle-import:PARTS_AMAN_RESISTOR_0603")
      (libsource (lib "eagle-import") (part "PARTS_AMAN_RESISTOR"))
    )
    (comp (ref "R55")
      (value "100k")
      (footprint "eagle-import:PARTS_AMAN_RESISTOR_0603")
      (libsource (lib "eagle-import") (part "PARTS_AMAN_RESISTOR"))
    )
    (comp (ref "R61")
      (value "10k")
      (footprint "eagle-import:PARTS_AMAN_RESISTOR_0603")
      (libsource (lib "eagle-import") (part "PARTS_AMAN_RESISTOR"))
    )
    (comp (ref "R62")
      (value "10k")
      (footprint "eagle-import:PARTS_AMAN_RESISTOR_0603")
      (libsource (lib "eagle-import") (part "PARTS_AMAN_RESISTOR"))
    )
    (comp (ref "R63")
      (value "10k")
      (footprint "eagle-import:PARTS_AMAN_RESISTOR_0603")
      (libsource (lib "eagle-import") (part "PARTS_AMAN_RESISTOR"))
    )
    (comp (ref "C7")
      (value "100n")
      (footprint "eagle-import:PARTS_AMAN_RESISTOR_0603")
      (libsource (lib "eagle-import") (part "PARTS_AMAN_CAPACITOR"))
    )
    (comp (ref "C9")
      (value "10u")
      (footprint "eagle-import:PANASONIC_B")
      (libsource (lib "eagle-import") (part "CPOL-EUB"))
    )
    (comp (ref "C10")
      (value "10u")
      (footprint "eagle-import:PANASONIC_B")
      (libsource (lib "eagle-import") (part "CPOL-EUB"))
    )
    (comp (ref "C19")
      (value "22u")
      (footprint "eagle-import:C1206")
      (libsource (lib "eagle-import") (part "C-USC1206"))
    )
    (comp (ref "C20")
      (value "22u")
      (footprint "eagle-import:C1206")
      (libsource (lib "eagle-import") (part "C-USC1206"))
    )
    (comp (ref "C24")
      (value "22u")
      (footprint "eagle-import:PANASONIC_C")
      (libsource (lib "eagle-import") (part "CPOL-EUC"))
    )
    (comp (ref "C25")
      (value "22u")
      (footprint "eagle-import:C1206")
      (libsource (lib "eagle-import") (part "C-USC1206"))
    )
    (comp (ref "C26")
      (value "22u")
      (footprint "eagle-import:PANASONIC_C")
      (libsource (lib "eagle-import") (part "CPOL-EUC"))
    )
    (comp (ref "C42")
      (value "1u")
      (footprint "eagle-import:PARTS_AMAN_RESISTOR_0603")
      (libsource (lib "eagle-import") (part "PARTS_AMAN_CAPACITOR"))
    )
    (comp (ref "C50")
      (value "10u")
      (footprint "eagle-import:PANASONIC_B")
      (libsource (lib "eagle-import") (part "CPOL-EUB"))
    )
    (comp (ref "D1")
      (value "1N5819HW")
      (footprint "eagle-import:SOD123")
      (libsource (lib "eagle-import") (part "DIODE-SOD123"))
    )
    (comp (ref "D3")
      (value "1N5819HW")
      (footprint "eagle-import:SOD123")
      (libsource (lib "eagle-import") (part "DIODE-SOD123"))
    )
    (comp (ref "IC3")
      (value "R-78E3.3-0.5")
      (footprint "eagle-import:WE78")
      (libsource (lib "eagle-import") (part "WE173950378"))
    )
    (comp (ref "IC5")
      (value "LD2981ABU33")
      (footprint "eagle-import:SOT89")
      (libsource (lib "eagle-import") (part "LD2981ABU"))
    )
    (comp (ref "IC10")
      (value "LM4040B10")
      (footprint "eagle-import:DBZ_R-PDSO-G3")
      (libsource (lib "eagle-import") (part "LM4041DBZB12"))
    )
    (comp (ref "JP5")
      (value "M05X2SHD")
      (footprint "eagle-import:2X5-SHROUDED")
      (libsource (lib "eagle-import") (part "M05X2SHD"))
    )
    (comp (ref "L1")
      (value "33u")
      (footprint "eagle-import:L2012C")
      (libsource (lib "eagle-import") (part "L-USL2012C"))
    )
    (comp (ref "L2")
      (value "WE-CBF_0603")
      (footprint "eagle-import:0603")
      (libsource (lib "eagle-import") (part "WE-CBF_0603"))
    )
    (comp (ref "L3")
      (value "WE-CBF_0603")
      (footprint "eagle-import:0603")
      (libsource (lib "eagle-import") (part "WE-CBF_0603"))
    )
    (comp (ref "L4")
      (value "WE-CBF_0603")
      (footprint "eagle-import:0603")
      (libsource (lib "eagle-import") (part "WE-CBF_0603"))
    )
    (comp (ref "R46")
      (value "1.5k")
      (footprint "eagle-import:PARTS_AMAN_RESISTOR_0603")
      (libsource (lib "eagle-import") (part "PARTS_AMAN_RESISTOR"))
    )
  )
  (nets
    (net (code "1") (name "+3V3") (class "Default")
      (node (ref "C1") (pin "1") (pinfunction "1_1") (pintype "passive"))
      (node (ref "C10") (pin "+") (pinfunction "+_+") (pintype "passive"))
      (node (ref "C15") (pin "1") (pinfunction "1_1") (pintype "passive"))
      (node (ref "C16") (pin "1") (pinfunction "1_1") (pintype "passive"))
      (node (ref "C3") (pin "1") (pinfunction "1_1") (pintype "passive"))
      (node (ref "C6") (pin "1") (pinfunction "1_1") (pintype "passive"))
      (node (ref "C7") (pin "1") (pinfunction "1_1") (pintype "passive"))
      (node (ref "IC1") (pin "1") (pinfunction "VBAT_1") (pintype "power_in"))
      (node (ref "IC1") (pin "17") (pinfunction "VDD_2_17") (pintype "power_in"))
      (node (ref "IC1") (pin "48") (pinfunction "VDD_1_48") (pintype "power_in"))
      (node (ref "IC3") (pin "3") (pinfunction "VO_3") (pintype "passive"))
      (node (ref "IC4") (pin "12") (pinfunction "DVDD_12") (pintype "power_in"))
      (node (ref "R3") (pin "1") (pinfunction "1_1") (pintype "passive"))
    )
    (net (code "2") (name "+3V3_A") (class "Default")
      (node (ref "C12") (pin "1") (pinfunction "1_1") (pintype "passive"))
      (node (ref "C13") (pin "1") (pinfunction "1_1") (pintype "passive"))
      (node (ref "C14") (pin "1") (pinfunction "1_1") (pintype "passive"))
      (node (ref "C17") (pin "1") (pinfunction "1_1") (pintype "passive"))
      (node (ref "C29") (pin "+") (pinfunction "+_+") (pintype "passive"))
      (node (ref "C30") (pin "1") (pinfunction "1_1") (pintype "passive"))
      (node (ref "C43") (pin "1") (pinfunction "1_1") (pintype "passive"))
      (node (ref "C5") (pin "1") (pinfunction "1_1") (pintype "passive"))
      (node (ref "C50") (pin "+") (pinfunction "+_+") (pintype "passive"))
      (node (ref "C8") (pin "1") (pinfunction "1_1") (pintype "passive"))
      (node (ref "C9") (pin "+") (pinfunction "+_+") (pintype "passive"))
      (node (ref "D2") (pin "2") (pinfunction "C_2") (pintype "passive"))
      (node (ref "IC1") (pin "24") (pinfunction "VDDSD_24") (pintype "power_in"))
      (node (ref "IC1") (pin "25") (pinfunction "VREFSD+_25") (pintype "power_in"))
      (node (ref "IC1") (pin "9") (pinfunction "VDDA_9") (pintype "power_in"))
      (node (ref "IC2") (pin "16") (pinfunction "VCC_16") (pintype "power_in"))
      (node (ref "IC4") (pin "4") (pinfunction "AVDD_4") (pintype "power_in"))
      (node (ref "IC5") (pin "1") (pinfunction "VO_1") (pintype "passive"))
      (node (ref "IC6") (pin "4") (pinfunction "V+_4") (pintype "power_in"))
      (node (ref "IC7") (pin "4") (pinfunction "V+_4") (pintype "power_in"))
      (node (ref "JP1") (pin "1") (pinfunction "1_1") (pintype "passive"))
    )
    (net (code "3") (name "ADC_CLOCK") (class "Default")
      (node (ref "C36") (pin "2") (pinfunction "2_2") (pintype "passive"))
      (node (ref "IC1") (pin "20") (pinfunction "PB2/SDADC1_AIN4P/SDADC2_AIN6P_20") (pintype "bidirectional"))
      (node (ref "IC7") (pin "1") (pinfunction "OUT_1") (pintype "output"))
      (node (ref "R37") (pin "1") (pinfunction "1_1") (pintype "passive"))
    )
    (net (code "4") (name "ADC_FM") (class "Default")
      (node (ref "C46") (pin "2") (pinfunction "2_2") (pintype "passive"))
      (node (ref "IC1") (pin "21") (pinfunction "PE8/SDADC1_AIN8P/SDADC2_AIN8P_21") (pintype "bidirectional"))
      (node (ref "IC7") (pin "7") (pinfunction "OUT_7") (pintype "output"))
      (node (ref "R52") (pin "1") (pinfunction "1_1") (pintype "passive"))
    )
    (net (code "5") (name "ADC_SHAPE") (class "Default")
      (node (ref "C32") (pin "2") (pinfunction "2_2") (pintype "passive"))
      (node (ref "IC1") (pin "27") (pinfunction "PB15/SPI2_MOSI/I2S2_SD/SDADC3_AIN7P/SDADC3_AIN8M_27") (pintype "bidirectional"))
      (node (ref "IC6") (pin "8") (pinfunction "OUT_8") (pintype "output"))
      (node (ref "R27") (pin "1") (pinfunction "1_1") (pintype "passive"))
    )
    (net (code "6") (name "ADC_SHIFT") (class "Default")
      (node (ref "C28") (pin "2") (pinfunction "2_2") (pintype "passive"))
      (node (ref "IC1") (pin "28") (pinfunction "PD8/SPI2_SCK/I2S2_CK/USART3_TX/SDADC3_AIN6P_28") (pintype "bidirectional"))
      (node (ref "IC6") (pin "14") (pinfunction "OUT_14") (pintype "output"))
      (node (ref "R19") (pin "1") (pinfunction "1_1") (pintype "passive"))
    )
    (net (code "7") (name "ADC_SLOPE") (class "Default")
      (node (ref "C27") (pin "2") (pinfunction "2_2") (pintype "passive"))
      (node (ref "IC1") (pin "18") (pinfunction "PB0/SPI1_MOSI/I2S1_SD/TIM3_CH3/ADC_IN8/SDADC1_AIN6P_18") (pintype "bidirectional"))
      (node (ref "IC6") (pin "1") (pinfunction "OUT_1") (pintype "output"))
      (node (ref "R18") (pin "1") (pinfunction "1_1") (pintype "passive"))
    )
    (net (code "8") (name "ADC_SMOOTHNESS") (class "Default")
      (node (ref "C41") (pin "2") (pinfunction "2_2") (pintype "passive"))
      (node (ref "IC1") (pin "26") (pinfunction "PB14/SPI2_MISO/I2S2_MCK/USART3_RTS/SDADC3_AIN8P_26") (pintype "bidirectional"))
      (node (ref "IC7") (pin "14") (pinfunction "OUT_14") (pintype "output"))
      (node (ref "R41") (pin "1") (pinfunction "1_1") (pintype "passive"))
    )
    (net (code "9") (name "ADC_TRIG") (class "Default")
      (node (ref "C31") (pin "2") (pinfunction "2_2") (pintype "passive"))
      (node (ref "IC1") (pin "19") (pinfunction "PB1/TIM3_CH4/ADC_IN9/SDADC1_AIN5P/SDADC1_AIN6M_19") (pintype "bidirectional"))
      (node (ref "IC6") (pin "7") (pinfunction "OUT_7") (pintype "output"))
      (node (ref "R28") (pin "1") (pinfunction "1_1") (pintype "passive"))
    )
    (net (code "10") (name "ADC_V_OCT") (class "Default")
      (node (ref "C47") (pin "2") (pinfunction "2_2") (pintype "passive"))
      (node (ref "IC1") (pin "22") (pinfunction "PE9/SDADC1_AIN7P/SDADC1_AIN8M/SDADC2_AIN7P/SDADC2_AIN8M_22") (pintype "bidirectional"))
      (node (ref "IC7") (pin "8") (pinfunction "OUT_8") (pintype "output"))
      (node (ref "R53") (pin "1") (pinfunction "1_1") (pintype "passive"))
    )
    (net (code "11") (name "AREF_-10") (class "Default")
      (node (ref "C42") (pin "1") (pinfunction "1_1") (pintype "passive"))
      (node (ref "IC10") (pin "2") (pinfunction "A_2") (pintype "passive"))
      (node (ref "R20") (pin "2") (pinfunction "2_2") (pintype "passive"))
      (node (ref "R21") (pin "2") (pinfunction "2_2") (pintype "passive"))
      (node (ref "R25") (pin "2") (pinfunction "2_2") (pintype "passive"))
      (node (ref "R26") (pin "2") (pinfunction "2_2") (pintype "passive"))
      (node (ref "R43") (pin "2") (pinfunction "2_2") (pintype "passive"))
      (node (ref "R44") (pin "2") (pinfunction "2_2") (pintype "passive"))
      (node (ref "R46") (pin "2") (pinfunction "2_2") (pintype "passive"))
      (node (ref "R50") (pin "2") (pinfunction "2_2") (pintype "passive"))
      (node (ref "R51") (pin "2") (pinfunction "2_2") (pintype "passive"))
    )
    (net (code "12") (name "DAC_1") (class "Default")
      (node (ref "IC4") (pin "1") (pinfunction "OUTA_1") (pintype "output"))
      (node (ref "R31") (pin "2") (pinfunction "2_2") (pintype "passive"))
    )
    (net (code "13") (name "DAC_2") (class "Default")
      (node (ref "IC4") (pin "2") (pinfunction "OUTB_2") (pintype "output"))
      (node (ref "R32") (pin "2") (pinfunction "2_2") (pintype "passive"))
    )
    (net (code "14") (name "DAC_3") (class "Default")
      (node (ref "IC4") (pin "7") (pinfunction "OUTC_7") (pintype "output"))
      (node (ref "R33") (pin "2") (pinfunction "2_2") (pintype "passive"))
    )
    (net (code "15") (name "DAC_4") (class "Default")
      (node (ref "IC4") (pin "8") (pinfunction "OUTD_8") (pintype "output"))
      (node (ref "R34") (pin "2") (pinfunction "2_2") (pintype "passive"))
    )
    (net (code "16") (name "DAC_MOSI") (class "Default")
      (node (ref "IC1") (pin "31") (pinfunction "PA10/SPI2_MOSI/I2S2_SD/I2C2_SDA/USART1_RX/TIM2_CH4_31") (pintype "bidirectional"))
      (node (ref "IC4") (pin "11") (pinfunction "IN_11") (pintype "input"))
    )
    (net (code "17") (name "DAC_SCK") (class "Default")
      (node (ref "IC1") (pin "29") (pinfunction "PA8/SPI2_SCK/I2S2_CK/I2C2_SMBA/USART1_CK/TIM5_CH1_29") (pintype "bidirectional"))
      (node (ref "IC4") (pin "10") (pinfunction "SCK_10") (pintype "input"))
    )
    (net (code "18") (name "DAC_SS") (class "Default")
      (node (ref "IC1") (pin "32") (pinfunction "PA11/SPI2_NSS/I2S2_WS/SPI1_NSS/I2S1_WS/USART1_CTS/CAN_RX/TIM4_CH1/TIM5_CH2_32") (pintype "bidirectional"))
      (node (ref "IC4") (pin "9") (pinfunction "SYNC_9") (pintype "input"))
    )
    (net (code "19") (name "FREQUENCY_POT") (class "Default")
      (node (ref "IC1") (pin "16") (pinfunction "PA6/SPI1_MISO/I2S1_MCK/TIM3_CH1/ADC_IN6/DAC2_OUT1_16") (pintype "bidirectional"))
      (node (ref "JP16") (pin "1") (pinfunction "1_1") (pintype "passive"))
    )
    (net (code "20") (name "GND") (class "Default")
      (node (ref "C1") (pin "2") (pinfunction "2_2") (pintype "passive"))
      (node (ref "C10") (pin "-") (pinfunction "-_-") (pintype "passive"))
      (node (ref "C11") (pin "1") (pinfunction "1_1") (pintype "passive"))
      (node (ref "C12") (pin "2") (pinfunction "2_2") (pintype "passive"))
      (node (ref "C13") (pin "2") (pinfunction "2_2") (pintype "passive"))
      (node (ref "C14") (pin "2") (pinfunction "2_2") (pintype "passive"))
      (node (ref "C15") (pin "2") (pinfunction "2_2") (pintype "passive"))
      (node (ref "C16") (pin "2") (pinfunction "2_2") (pintype "passive"))
      (node (ref "C17") (pin "2") (pinfunction "2_2") (pintype "passive"))
      (node (ref "C18") (pin "2") (pinfunction "2_2") (pintype "passive"))
      (node (ref "C19") (pin "2") (pinfunction "2_2") (pintype "passive"))
      (node (ref "C2") (pin "2") (pinfunction "2_2") (pintype "passive"))
      (node (ref "C20") (pin "2") (pinfunction "2_2") (pintype "passive"))
      (node (ref "C21") (pin "2") (pinfunction "2_2") (pintype "passive"))
      (node (ref "C24") (pin "-") (pinfunction "-_-") (pintype "passive"))
      (node (ref "C25") (pin "2") (pinfunction "2_2") (pintype "passive"))
      (node (ref "C26") (pin "+") (pinfunction "+_+") (pintype "passive"))
      (node (ref "C29") (pin "-") (pinfunction "-_-") (pintype "passive"))
      (node (ref "C3") (pin "2") (pinfunction "2_2") (pintype "passive"))
      (node (ref "C30") (pin "2") (pinfunction "2_2") (pintype "passive"))
      (node (ref "C33") (pin "1") (pinfunction "1_1") (pintype "passive"))
      (node (ref "C34") (pin "1") (pinfunction "1_1") (pintype "passive"))
      (node (ref "C4") (pin "1") (pinfunction "1_1") (pintype "passive"))
      (node (ref "C42") (pin "2") (pinfunction "2_2") (pintype "passive"))
      (node (ref "C43") (pin "2") (pinfunction "2_2") (pintype "passive"))
      (node (ref "C48") (pin "2") (pinfunction "2_2") (pintype "passive"))
      (node (ref "C49") (pin "2") (pinfunction "2_2") (pintype "passive"))
      (node (ref "C5") (pin "2") (pinfunction "2_2") (pintype "passive"))
      (node (ref "C50") (pin "-") (pinfunction "-_-") (pintype "passive"))
      (node (ref "C56") (pin "2") (pinfunction "2_2") (pintype "passive"))
      (node (ref "C6") (pin "2") (pinfunction "2_2") (pintype "passive"))
      (node (ref "C7") (pin "2") (pinfunction "2_2") (pintype "passive"))
      (node (ref "C8") (pin "2") (pinfunction "2_2") (pintype "passive"))
      (node (ref "C9") (pin "-") (pinfunction "-_-") (pintype "passive"))
      (node (ref "D10") (pin "1") (pinfunction "A_1") (pintype "passive"))
      (node (ref "D11") (pin "1") (pinfunction "A_1") (pintype "passive"))
      (node (ref "D2") (pin "1") (pinfunction "A_1") (pintype "passive"))
      (node (ref "D4") (pin "1") (pinfunction "A_1") (pintype "passive"))
      (node (ref "D5") (pin "1") (pinfunction "A_1") (pintype "passive"))
      (node (ref "D6") (pin "1") (pinfunction "A_1") (pintype "passive"))
      (node (ref "D7") (pin "1") (pinfunction "A_1") (pintype "passive"))
      (node (ref "D8") (pin "1") (pinfunction "A_1") (pintype "passive"))
      (node (ref "D9") (pin "1") (pinfunction "A_1") (pintype "passive"))
      (node (ref "IC1") (pin "23") (pinfunction "VSSSD/VREFSD-_23") (pintype "power_in"))
      (node (ref "IC1") (pin "44") (pinfunction "BOOT0_44") (pintype "bidirectional"))
      (node (ref "IC1") (pin "47") (pinfunction "VSS_1_47") (pintype "power_in"))
      (node (ref "IC1") (pin "8") (pinfunction "VSSA_8") (pintype "power_in"))
      (node (ref "IC10") (pin "1") (pinfunction "C_1") (pintype "passive"))
      (node (ref "IC2") (pin "6") (pinfunction "INH_6") (pintype "input"))
      (node (ref "IC2") (pin "7") (pinfunction "VEE_7") (pintype "power_in"))
      (node (ref "IC2") (pin "8") (pinfunction "GND_8") (pintype "power_in"))
      (node (ref "IC3") (pin "2") (pinfunction "GND_2") (pintype "passive"))
      (node (ref "IC4") (pin "13") (pinfunction "A0_13") (pintype "input"))
      (node (ref "IC4") (pin "14") (pinfunction "A1_14") (pintype "input"))
      (node (ref "IC4") (pin "15") (pinfunction "ENABLE_15") (pintype "input"))
      (node (ref "IC4") (pin "16") (pinfunction "LDAC_16") (pintype "input"))
      (node (ref "IC4") (pin "5") (pinfunction "VREFL_5") (pintype "bidirectional"))
      (node (ref "IC4") (pin "6") (pinfunction "GND_6") (pintype "power_in"))
      (node (ref "IC5") (pin "2") (pinfunction "GND_2") (pintype "passive"))
      (node (ref "IC6") (pin "10") (pinfunction "+IN_10") (pintype "input"))
      (node (ref "IC6") (pin "11") (pinfunction "V-_11") (pintype "power_in"))
      (node (ref "IC6") (pin "12") (pinfunction "+IN_12") (pintype "input"))
      (node (ref "IC6") (pin "3") (pinfunction "+IN_3") (pintype "input"))
      (node (ref "IC6") (pin "5") (pinfunction "+IN_5") (pintype "input"))
      (node (ref "IC7") (pin "10") (pinfunction "+IN_10") (pintype "input"))
      (node (ref "IC7") (pin "11") (pinfunction "V-_11") (pintype "power_in"))
      (node (ref "IC7") (pin "12") (pinfunction "+IN_12") (pintype "input"))
      (node (ref "IC7") (pin "3") (pinfunction "+IN_3") (pintype "input"))
      (node (ref "IC7") (pin "5") (pinfunction "+IN_5") (pintype "input"))
      (node (ref "JP5") (pin "3") (pinfunction "3_3") (pintype "passive"))
      (node (ref "JP5") (pin "4") (pinfunction "4_4") (pintype "passive"))
      (node (ref "JP5") (pin "5") (pinfunction "5_5") (pintype "passive"))
      (node (ref "JP5") (pin "6") (pinfunction "6_6") (pintype "passive"))
      (node (ref "JP5") (pin "7") (pinfunction "7_7") (pintype "passive"))
      (node (ref "JP5") (pin "8") (pinfunction "8_8") (pintype "passive"))
      (node (ref "JP50") (pin "1") (pinfunction "1_1") (pintype "passive"))
      (node (ref "JP51") (pin "1") (pinfunction "1_1") (pintype "passive"))
      (node (ref "JP52") (pin "1") (pinfunction "1_1") (pintype "passive"))
      (node (ref "JP6") (pin "1") (pinfunction "1_1") (pintype "passive"))
      (node (ref "Q1") (pin "2") (pinfunction "LID1_2") (pintype "power_in"))
      (node (ref "Q1") (pin "4") (pinfunction "LID2_4") (pintype "power_in"))
      (node (ref "R15") (pin "1") (pinfunction "1_1") (pintype "passive"))
      (node (ref "R64") (pin "2") (pinfunction "2_2") (pintype "passive"))
      (node (ref "R65") (pin "2") (pinfunction "2_2") (pintype "passive"))
      (node (ref "R66") (pin "2") (pinfunction "2_2") (pintype "passive"))
      (node (ref "R67") (pin "2") (pinfunction "2_2") (pintype "passive"))
    )
    (net (code "21") (name "LED_MODE_G") (class "Default")
      (node (ref "IC1") (pin "35") (pinfunction "PF6/SPI1_MOSI/I2S1_SD/USART3_RTS/TIM4_CH4/I2C2_SCL_35") (pintype "bidirectional"))
      (node (ref "JP24") (pin "1") (pinfunction "1_1") (pintype "passive"))
    )
    (net (code "22") (name "LED_MODE_R") (class "Default")
      (node (ref "IC1") (pin "36") (pinfunction "PF7/I2C2_SDA/USART2_CK_36") (pintype "bidirectional"))
      (node (ref "JP23") (pin "1") (pinfunction "1_1") (pintype "passive"))
    )
    (net (code "23") (name "LED_RANGE_G") (class "Default")
      (node (ref "IC1") (pin "42") (pinfunction "PB6/I2C1_SCL/USART1_TX/TIM4_CH1_42") (pintype "bidirectional"))
      (node (ref "JP22") (pin "1") (pinfunction "1_1") (pintype "passive"))
    )
    (net (code "24") (name "LED_RANGE_R") (class "Default")
      (node (ref "IC1") (pin "41") (pinfunction "PB5/SPI1_MOSI/I2S1_SD/SPI3_MOSI/I2S3_SD/I2C1_SMBAI/USART2_CK/TIM3_CH2_41") (pintype "bidirectional"))
      (node (ref "JP21") (pin "1") (pinfunction "1_1") (pintype "passive"))
    )
    (net (code "25") (name "LED_SHIFT_G") (class "Default")
      (node (ref "IC1") (pin "40") (pinfunction "PB4/SPI1_MISO/I2S1_MCK/SPI3_MISO/I2S3_MCK/USART2_RX/TIM3_CH1/NJTRST_40") (pintype "bidirectional"))
      (node (ref "JP26") (pin "1") (pinfunction "1_1") (pintype "passive"))
    )
    (net (code "26") (name "LED_SHIFT_R") (class "Default")
      (node (ref "IC1") (pin "39") (pinfunction "PB3/SPI1_SCK/I2S1_CK/SPI3_SCK/I2S3_CK/USART2_TX/TIM2_CH2/JTDO/SPI3_SCK/JTDO_39") (pintype "bidirectional"))
      (node (ref "JP25") (pin "1") (pinfunction "1_1") (pintype "passive"))
    )
    (net (code "27") (name "MUXED_POTS") (class "Default")
      (node (ref "C56") (pin "1") (pinfunction "1_1") (pintype "passive"))
      (node (ref "IC1") (pin "11") (pinfunction "PA1/SPI3_SCK/I2S3_CK/USART2_RTS/TIM2_CH2/TIM5_CH2/ADC_IN1_11") (pintype "bidirectional"))
      (node (ref "IC2") (pin "3") (pinfunction "X_3") (pintype "bidirectional"))
    )
    (net (code "28") (name "MUX_ADDR_0") (class "Default")
      (node (ref "IC1") (pin "13") (pinfunction "PA3/SPI3_MOSI/I2S3_SD/USART2_RX/TIM2_CH4/TIM5_CH4/ADC_IN3_13") (pintype "bidirectional"))
      (node (ref "IC2") (pin "11") (pinfunction "A_11") (pintype "input"))
    )
    (net (code "29") (name "MUX_ADDR_1") (class "Default")
      (node (ref "IC1") (pin "14") (pinfunction "PA4/SPI1_NSS/I2S1_WS/SPI3_NSS/I2S3_WS/USART2_CK/TIM3_CH2/ADC_IN4/DAC1_OUT1_14") (pintype "bidirectional"))
      (node (ref "IC2") (pin "10") (pinfunction "B_10") (pintype "input"))
    )
    (net (code "30") (name "MUX_ADDR_2") (class "Default")
      (node (ref "IC1") (pin "15") (pinfunction "PA5/SPI1_SCK/I2S1_CK/TIM2_CH1/ADC_IN5/DAC1_OUT2_15") (pintype "bidirectional"))
      (node (ref "IC2") (pin "9") (pinfunction "C_9") (pintype "input"))
    )
    (net (code "31") (name "NORMALIZATION_PROBE") (class "Default")
      (node (ref "D2") (pin "3") (pinfunction "AC_3") (pintype "passive"))
      (node (ref "IC1") (pin "30") (pinfunction "PA9/SPI_MISO/I2S2_MCK/I2C2_SCL/USART1_TX/TIM2_CH3_30") (pintype "bidirectional"))
      (node (ref "R61") (pin "2") (pinfunction "2_2") (pintype "passive"))
      (node (ref "R62") (pin "2") (pinfunction "2_2") (pintype "passive"))
      (node (ref "R63") (pin "2") (pinfunction "2_2") (pintype "passive"))
    )
    (net (code "32") (name "Net-(C11-Pad2)") (class "Default")
      (node (ref "C11") (pin "2") (pinfunction "2_2") (pintype "passive"))
      (node (ref "Q1") (pin "1") (pinfunction "1_1") (pintype "passive"))
      (node (ref "R9") (pin "2") (pinfunction "2_2") (pintype "passive"))
    )
    (net (code "33") (name "Net-(C20-Pad1)") (class "Default")
      (node (ref "C20") (pin "1") (pinfunction "1_1") (pintype "passive"))
      (node (ref "D1") (pin "C") (pinfunction "C_C") (pintype "passive"))
      (node (ref "L1") (pin "1") (pinfunction "1_1") (pintype "passive"))
      (node (ref "L2") (pin "2") (pinfunction "2_2") (pintype "passive"))
      (node (ref "L3") (pin "2") (pinfunction "2_2") (pintype "passive"))
    )
    (net (code "34") (name "Net-(D1-PadA)") (class "Default")
      (node (ref "D1") (pin "A") (pinfunction "A_A") (pintype "passive"))
      (node (ref "JP5") (pin "10") (pinfunction "10_10") (pintype "passive"))
      (node (ref "JP5") (pin "9") (pinfunction "9_9") (pintype "passive"))
    )
    (net (code "35") (name "Net-(D3-PadA)") (class "Default")
      (node (ref "D3") (pin "A") (pinfunction "A_A") (pintype "passive"))
      (node (ref "L4") (pin "2") (pinfunction "2_2") (pintype "passive"))
    )
    (net (code "36") (name "Net-(D3-PadC)") (class "Default")
      (node (ref "D3") (pin "C") (pinfunction "C_C") (pintype "passive"))
      (node (ref "JP5") (pin "1") (pinfunction "1_1") (pintype "passive"))
      (node (ref "JP5") (pin "2") (pinfunction "2_2") (pintype "passive"))
    )
    (net (code "37") (name "Net-(D4-C)") (class "Default")
      (node (ref "D4") (pin "2") (pinfunction "C_2") (pintype "passive"))
      (node (ref "JP27") (pin "1") (pinfunction "1_1") (pintype "passive"))
      (node (ref "R30") (pin "2") (pinfunction "2_2") (pintype "passive"))
    )
    (net (code "38") (name "Net-(D5-C)") (class "Default")
      (node (ref "D5") (pin "2") (pinfunction "C_2") (pintype "passive"))
      (node (ref "JP30") (pin "1") (pinfunction "1_1") (pintype "passive"))
      (node (ref "R17") (pin "2") (pinfunction "2_2") (pintype "passive"))
    )
    (net (code "39") (name "Net-(D6-C)") (class "Default")
      (node (ref "D6") (pin "2") (pinfunction "C_2") (pintype "passive"))
      (node (ref "JP28") (pin "1") (pinfunction "1_1") (pintype "passive"))
      (node (ref "R36") (pin "2") (pinfunction "2_2") (pintype "passive"))
    )
    (net (code "40") (name "Net-(D7-C)") (class "Default")
      (node (ref "D7") (pin "2") (pinfunction "C_2") (pintype "passive"))
      (node (ref "JP29") (pin "1") (pinfunction "1_1") (pintype "passive"))
      (node (ref "R54") (pin "2") (pinfunction "2_2") (pintype "passive"))
    )
    (net (code "41") (name "Net-(D8-C)") (class "Default")
      (node (ref "D8") (pin "2") (pinfunction "C_2") (pintype "passive"))
      (node (ref "JP31") (pin "1") (pinfunction "1_1") (pintype "passive"))
      (node (ref "R16") (pin "2") (pinfunction "2_2") (pintype "passive"))
    )
    (net (code "42") (name "Net-(D9-C)") (class "Default")
      (node (ref "D9") (pin "2") (pinfunction "C_2") (pintype "passive"))
      (node (ref "JP32") (pin "1") (pinfunction "1_1") (pintype "passive"))
      (node (ref "R55") (pin "2") (pinfunction "2_2") (pintype "passive"))
    )
    (net (code "43") (name "Net-(D10-C)") (class "Default")
      (node (ref "D10") (pin "2") (pinfunction "C_2") (pintype "passive"))
      (node (ref "JP34") (pin "1") (pinfunction "1_1") (pintype "passive"))
      (node (ref "R29") (pin "2") (pinfunction "2_2") (pintype "passive"))
    )
    (net (code "44") (name "Net-(D11-C)") (class "Default")
      (node (ref "D11") (pin "2") (pinfunction "C_2") (pintype "passive"))
      (node (ref "JP36") (pin "1") (pinfunction "1_1") (pintype "passive"))
      (node (ref "R35") (pin "2") (pinfunction "2_2") (pintype "passive"))
    )
    (net (code "45") (name "Net-(IC1-PF0{slash}OSC_IN{slash}I2C2_SDA)") (class "Default")
      (node (ref "IC1") (pin "5") (pinfunction "PF0/OSC_IN/I2C2_SDA_5") (pintype "bidirectional"))
      (node (ref "R8") (pin "1") (pinfunction "1_1") (pintype "passive"))
    )
    (net (code "46") (name "Net-(IC1-PF1{slash}OSC_OUT{slash}I2C2_SCL)") (class "Default")
      (node (ref "IC1") (pin "6") (pinfunction "PF1/OSC_OUT/I2C2_SCL_6") (pintype "bidirectional"))
      (node (ref "R9") (pin "1") (pinfunction "1_1") (pintype "passive"))
    )
    (net (code "47") (name "Net-(IC2A-X0)") (class "Default")
      (node (ref "IC2") (pin "13") (pinfunction "X0_13") (pintype "bidirectional"))
      (node (ref "JP9") (pin "1") (pinfunction "1_1") (pintype "passive"))
    )
    (net (code "48") (name "Net-(IC2A-X1)") (class "Default")
      (node (ref "IC2") (pin "14") (pinfunction "X1_14") (pintype "bidirectional"))
      (node (ref "JP14") (pin "1") (pinfunction "1_1") (pintype "passive"))
    )
    (net (code "49") (name "Net-(IC2A-X2)") (class "Default")
      (node (ref "IC2") (pin "15") (pinfunction "X2_15") (pintype "bidirectional"))
      (node (ref "JP15") (pin "1") (pinfunction "1_1") (pintype "passive"))
    )
    (net (code "50") (name "Net-(IC2A-X3)") (class "Default")
      (node (ref "IC2") (pin "12") (pinfunction "X3_12") (pintype "bidirectional"))
      (node (ref "JP8") (pin "1") (pinfunction "1_1") (pintype "passive"))
    )
    (net (code "51") (name "Net-(IC2A-X4)") (class "Default")
      (node (ref "IC2") (pin "1") (pinfunction "X4_1") (pintype "bidirectional"))
      (node (ref "JP10") (pin "1") (pinfunction "1_1") (pintype "passive"))
    )
    (net (code "52") (name "Net-(IC2A-X5)") (class "Default")
      (node (ref "IC2") (pin "5") (pinfunction "X5_5") (pintype "bidirectional"))
      (node (ref "JP12") (pin "1") (pinfunction "1_1") (pintype "passive"))
    )
    (net (code "53") (name "Net-(IC2A-X6)") (class "Default")
      (node (ref "IC2") (pin "2") (pinfunction "X6_2") (pintype "bidirectional"))
      (node (ref "JP11") (pin "1") (pinfunction "1_1") (pintype "passive"))
    )
    (net (code "54") (name "Net-(IC2A-X7)") (class "Default")
      (node (ref "IC2") (pin "4") (pinfunction "X7_4") (pintype "bidirectional"))
      (node (ref "JP13") (pin "1") (pinfunction "1_1") (pintype "passive"))
    )
    (net (code "55") (name "Net-(IC3-VI)") (class "Default")
      (node (ref "C19") (pin "1") (pinfunction "1_1") (pintype "passive"))
      (node (ref "IC3") (pin "1") (pinfunction "VI_1") (pintype "input"))
      (node (ref "L1") (pin "2") (pinfunction "2_2") (pintype "passive"))
    )
    (net (code "56") (name "Net-(IC5-VI)") (class "Default")
      (node (ref "C25") (pin "1") (pinfunction "1_1") (pintype "passive"))
      (node (ref "IC5") (pin "3") (pinfunction "VI_3") (pintype "input"))
      (node (ref "L3") (pin "1") (pinfunction "1_1") (pintype "passive"))
    )
    (net (code "57") (name "Net-(IC6A--IN)") (class "Default")
      (node (ref "C27") (pin "1") (pinfunction "1_1") (pintype "passive"))
      (node (ref "IC6") (pin "2") (pinfunction "-IN_2") (pintype "input"))
      (node (ref "R16") (pin "1") (pinfunction "1_1") (pintype "passive"))
      (node (ref "R18") (pin "2") (pinfunction "2_2") (pintype "passive"))
      (node (ref "R20") (pin "1") (pinfunction "1_1") (pintype "passive"))
    )
    (net (code "58") (name "Net-(IC6B--IN)") (class "Default")
      (node (ref "C31") (pin "1") (pinfunction "1_1") (pintype "passive"))
      (node (ref "IC6") (pin "6") (pinfunction "-IN_6") (pintype "input"))
      (node (ref "R26") (pin "1") (pinfunction "1_1") (pintype "passive"))
      (node (ref "R28") (pin "2") (pinfunction "2_2") (pintype "passive"))
      (node (ref "R29") (pin "1") (pinfunction "1_1") (pintype "passive"))
    )
    (net (code "59") (name "Net-(IC6C--IN)") (class "Default")
      (node (ref "C32") (pin "1") (pinfunction "1_1") (pintype "passive"))
      (node (ref "IC6") (pin "9") (pinfunction "-IN_9") (pintype "input"))
      (node (ref "R25") (pin "1") (pinfunction "1_1") (pintype "passive"))
      (node (ref "R27") (pin "2") (pinfunction "2_2") (pintype "passive"))
      (node (ref "R30") (pin "1") (pinfunction "1_1") (pintype "passive"))
    )
    (net (code "60") (name "Net-(IC6D--IN)") (class "Default")
      (node (ref "C28") (pin "1") (pinfunction "1_1") (pintype "passive"))
      (node (ref "IC6") (pin "13") (pinfunction "-IN_13") (pintype "input"))
      (node (ref "R17") (pin "1") (pinfunction "1_1") (pintype "passive"))
      (node (ref "R19") (pin "2") (pinfunction "2_2") (pintype "passive"))
      (node (ref "R21") (pin "1") (pinfunction "1_1") (pintype "passive"))
    )
    (net (code "61") (name "Net-(IC7A--IN)") (class "Default")
      (node (ref "C36") (pin "1") (pinfunction "1_1") (pintype "passive"))
      (node (ref "IC7") (pin "2") (pinfunction "-IN_2") (pintype "input"))
      (node (ref "R35") (pin "1") (pinfunction "1_1") (pintype "passive"))
      (node (ref "R37") (pin "2") (pinfunction "2_2") (pintype "passive"))
      (node (ref "R44") (pin "1") (pinfunction "1_1") (pintype "passive"))
    )
    (net (code "62") (name "Net-(IC7B--IN)") (class "Default")
      (node (ref "C46") (pin "1") (pinfunction "1_1") (pintype "passive"))
      (node (ref "IC7") (pin "6") (pinfunction "-IN_6") (pintype "input"))
      (node (ref "R51") (pin "1") (pinfunction "1_1") (pintype "passive"))
      (node (ref "R52") (pin "2") (pinfunction "2_2") (pintype "passive"))
      (node (ref "R55") (pin "1") (pinfunction "1_1") (pintype "passive"))
    )
    (net (code "63") (name "Net-(IC7C--IN)") (class "Default")
      (node (ref "C47") (pin "1") (pinfunction "1_1") (pintype "passive"))
      (node (ref "IC7") (pin "9") (pinfunction "-IN_9") (pintype "input"))
      (node (ref "R50") (pin "1") (pinfunction "1_1") (pintype "passive"))
      (node (ref "R53") (pin "2") (pinfunction "2_2") (pintype "passive"))
      (node (ref "R54") (pin "1") (pinfunction "1_1") (pintype "passive"))
    )
    (net (code "64") (name "Net-(IC7D--IN)") (class "Default")
      (node (ref "C41") (pin "1") (pinfunction "1_1") (pintype "passive"))
      (node (ref "IC7") (pin "13") (pinfunction "-IN_13") (pintype "input"))
      (node (ref "R36") (pin "1") (pinfunction "1_1") (pintype "passive"))
      (node (ref "R41") (pin "2") (pinfunction "2_2") (pintype "passive"))
      (node (ref "R43") (pin "1") (pinfunction "1_1") (pintype "passive"))
    )
    (net (code "65") (name "Net-(IC8A-+IN)") (class "Default")
      (node (ref "C39") (pin "2") (pinfunction "2_2") (pintype "passive"))
      (node (ref "IC8") (pin "14") (pinfunction "OUT_14") (pintype "output"))
      (node (ref "IC8") (pin "3") (pinfunction "+IN_3") (pintype "input"))
      (node (ref "R48") (pin "2") (pinfunction "2_2") (pintype "passive"))
    )
    (net (code "66") (name "Net-(IC8A--IN)") (class "Default")
      (node (ref "IC8") (pin "2") (pinfunction "-IN_2") (pintype "input"))
      (node (ref "JP47") (pin "1") (pinfunction "1_1") (pintype "passive"))
      (node (ref "R66") (pin "1") (pinfunction "1_1") (pintype "passive"))
    )
    (net (code "67") (name "Net-(IC8A-OUT)") (class "Default")
      (node (ref "IC8") (pin "1") (pinfunction "OUT_1") (pintype "output"))
      (node (ref "JP46") (pin "1") (pinfunction "1_1") (pintype "passive"))
    )
    (net (code "68") (name "Net-(IC8B-+IN)") (class "Default")
      (node (ref "C40") (pin "2") (pinfunction "2_2") (pintype "passive"))
      (node (ref "IC8") (pin "5") (pinfunction "+IN_5") (pintype "input"))
      (node (ref "IC8") (pin "8") (pinfunction "OUT_8") (pintype "output"))
      (node (ref "R49") (pin "2") (pinfunction "2_2") (pintype "passive"))
    )
    (net (code "69") (name "Net-(IC8B--IN)") (class "Default")
      (node (ref "IC8") (pin "6") (pinfunction "-IN_6") (pintype "input"))
      (node (ref "JP49") (pin "1") (pinfunction "1_1") (pintype "passive"))
      (node (ref "R67") (pin "1") (pinfunction "1_1") (pintype "passive"))
    )
    (net (code "70") (name "Net-(IC8B-OUT)") (class "Default")
      (node (ref "IC8") (pin "7") (pinfunction "OUT_7") (pintype "output"))
      (node (ref "JP48") (pin "1") (pinfunction "1_1") (pintype "passive"))
    )
    (net (code "71") (name "Net-(IC8C--IN)") (class "Default")
      (node (ref "C40") (pin "1") (pinfunction "1_1") (pintype "passive"))
      (node (ref "IC8") (pin "9") (pinfunction "-IN_9") (pintype "input"))
      (node (ref "R34") (pin "1") (pinfunction "1_1") (pintype "passive"))
      (node (ref "R40") (pin "2") (pinfunction "2_2") (pintype "passive"))
    )
    (net (code "72") (name "Net-(IC8D--IN)") (class "Default")
      (node (ref "C39") (pin "1") (pinfunction "1_1") (pintype "passive"))
      (node (ref "IC8") (pin "13") (pinfunction "-IN_13") (pintype "input"))
      (node (ref "R33") (pin "1") (pinfunction "1_1") (pintype "passive"))
      (node (ref "R39") (pin "2") (pinfunction "2_2") (pintype "passive"))
    )
    (net (code "73") (name "Net-(IC9A-+IN)") (class "Default")
      (node (ref "C37") (pin "2") (pinfunction "2_2") (pintype "passive"))
      (node (ref "IC9") (pin "14") (pinfunction "OUT_14") (pintype "output"))
      (node (ref "IC9") (pin "3") (pinfunction "+IN_3") (pintype "input"))
      (node (ref "R47") (pin "2") (pinfunction "2_2") (pintype "passive"))
    )
    (net (code "74") (name "Net-(IC9A--IN)") (class "Default")
      (node (ref "IC9") (pin "2") (pinfunction "-IN_2") (pintype "input"))
      (node (ref "JP43") (pin "1") (pinfunction "1_1") (pintype "passive"))
      (node (ref "R64") (pin "1") (pinfunction "1_1") (pintype "passive"))
    )
    (net (code "75") (name "Net-(IC9A-OUT)") (class "Default")
      (node (ref "IC9") (pin "1") (pinfunction "OUT_1") (pintype "output"))
      (node (ref "JP42") (pin "1") (pinfunction "1_1") (pintype "passive"))
    )
    (net (code "76") (name "Net-(IC9B-+IN)") (class "Default")
      (node (ref "C38") (pin "2") (pinfunction "2_2") (pintype "passive"))
      (node (ref "IC9") (pin "5") (pinfunction "+IN_5") (pintype "input"))
      (node (ref "IC9") (pin "8") (pinfunction "OUT_8") (pintype "output"))
      (node (ref "R45") (pin "2") (pinfunction "2_2") (pintype "passive"))
    )
    (net (code "77") (name "Net-(IC9B--IN)") (class "Default")
      (node (ref "IC9") (pin "6") (pinfunction "-IN_6") (pintype "input"))
      (node (ref "JP45") (pin "1") (pinfunction "1_1") (pintype "passive"))
      (node (ref "R65") (pin "1") (pinfunction "1_1") (pintype "passive"))
    )
    (net (code "78") (name "Net-(IC9B-OUT)") (class "Default")
      (node (ref "IC9") (pin "7") (pinfunction "OUT_7") (pintype "output"))
      (node (ref "JP44") (pin "1") (pinfunction "1_1") (pintype "passive"))
    )
    (net (code "79") (name "Net-(IC9C--IN)") (class "Default")
      (node (ref "C38") (pin "1") (pinfunction "1_1") (pintype "passive"))
      (node (ref "IC9") (pin "9") (pinfunction "-IN_9") (pintype "input"))
      (node (ref "R32") (pin "1") (pinfunction "1_1") (pintype "passive"))
      (node (ref "R38") (pin "2") (pinfunction "2_2") (pintype "passive"))
    )
    (net (code "80") (name "Net-(IC9D--IN)") (class "Default")
      (node (ref "C37") (pin "1") (pinfunction "1_1") (pintype "passive"))
      (node (ref "IC9") (pin "13") (pinfunction "-IN_13") (pintype "input"))
      (node (ref "R31") (pin "1") (pinfunction "1_1") (pintype "passive"))
      (node (ref "R42") (pin "2") (pinfunction "2_2") (pintype "passive"))
    )
    (net (code "81") (name "Net-(JP7-Pad1)") (class "Default")
      (node (ref "JP7") (pin "1") (pinfunction "1_1") (pintype "passive"))
      (node (ref "R4") (pin "1") (pinfunction "1_1") (pintype "passive"))
    )
    (net (code "82") (name "Net-(JP7-Pad2)") (class "Default")
      (node (ref "JP7") (pin "2") (pinfunction "2_2") (pintype "passive"))
      (node (ref "R5") (pin "1") (pinfunction "1_1") (pintype "passive"))
    )
    (net (code "83") (name "Net-(JP33-Pad1)") (class "Default")
      (node (ref "JP33") (pin "1") (pinfunction "1_1") (pintype "passive"))
      (node (ref "R61") (pin "1") (pinfunction "1_1") (pintype "passive"))
    )
    (net (code "84") (name "Net-(JP35-Pad1)") (class "Default")
      (node (ref "JP35") (pin "1") (pinfunction "1_1") (pintype "passive"))
      (node (ref "R62") (pin "1") (pinfunction "1_1") (pintype "passive"))
    )
    (net (code "85") (name "Net-(JP37-Pad1)") (class "Default")
      (node (ref "JP37") (pin "1") (pinfunction "1_1") (pintype "passive"))
      (node (ref "R63") (pin "1") (pinfunction "1_1") (pintype "passive"))
    )
    (net (code "86") (name "Net-(JP38-Pad1)") (class "Default")
      (node (ref "JP38") (pin "1") (pinfunction "1_1") (pintype "passive"))
      (node (ref "R42") (pin "1") (pinfunction "1_1") (pintype "passive"))
      (node (ref "R47") (pin "1") (pinfunction "1_1") (pintype "passive"))
    )
    (net (code "87") (name "Net-(JP39-Pad1)") (class "Default")
      (node (ref "JP39") (pin "1") (pinfunction "1_1") (pintype "passive"))
      (node (ref "R38") (pin "1") (pinfunction "1_1") (pintype "passive"))
      (node (ref "R45") (pin "1") (pinfunction "1_1") (pintype "passive"))
    )
    (net (code "88") (name "Net-(JP40-Pad1)") (class "Default")
      (node (ref "JP40") (pin "1") (pinfunction "1_1") (pintype "passive"))
      (node (ref "R39") (pin "1") (pinfunction "1_1") (pintype "passive"))
      (node (ref "R48") (pin "1") (pinfunction "1_1") (pintype "passive"))
    )
    (net (code "89") (name "Net-(JP41-Pad1)") (class "Default")
      (node (ref "JP41") (pin "1") (pinfunction "1_1") (pintype "passive"))
      (node (ref "R40") (pin "1") (pinfunction "1_1") (pintype "passive"))
      (node (ref "R49") (pin "1") (pinfunction "1_1") (pintype "passive"))
    )
    (net (code "90") (name "Net-(Q1B-2)") (class "Default")
      (node (ref "C4") (pin "2") (pinfunction "2_2") (pintype "passive"))
      (node (ref "Q1") (pin "3") (pinfunction "2_3") (pintype "passive"))
      (node (ref "R8") (pin "2") (pinfunction "2_2") (pintype "passive"))
    )
    (net (code "91") (name "RESET") (class "Default")
      (node (ref "C2") (pin "1") (pinfunction "1_1") (pintype "passive"))
      (node (ref "IC1") (pin "7") (pinfunction "NRST_7") (pintype "bidirectional"))
      (node (ref "JP6") (pin "4") (pinfunction "4_4") (pintype "passive"))
      (node (ref "R3") (pin "2") (pinfunction "2_2") (pintype "passive"))
    )
    (net (code "92") (name "RX") (class "Default")
      (node (ref "IC1") (pin "46") (pinfunction "PB9/SPI2_NSS/I2S2_WS/I2C1_SDA/USART3_RX/CAN_TX/TIM4_CH4_46") (pintype "bidirectional"))
      (node (ref "R4") (pin "2") (pinfunction "2_2") (pintype "passive"))
    )
    (net (code "93") (name "SHAPE_POT") (class "Default")
      (node (ref "IC1") (pin "10") (pinfunction "PA0/USART2_CTS/TIM2_CH1/TIM5_CH1/ADC_IN0_10") (pintype "bidirectional"))
      (node (ref "JP17") (pin "1") (pinfunction "1_1") (pintype "passive"))
    )
    (net (code "94") (name "SWCLK") (class "Default")
      (node (ref "IC1") (pin "37") (pinfunction "PA14/I2C1_SDA/JTCK-SWCLK_37") (pintype "bidirectional"))
      (node (ref "JP6") (pin "3") (pinfunction "3_3") (pintype "passive"))
    )
    (net (code "95") (name "SWDIO") (class "Default")
      (node (ref "IC1") (pin "34") (pinfunction "PA13/SPI1_MISO/I2S1_MCK/USART3_CTS/TIM4_CH3/TIM5_CH4/JTMS-SWDIO_34") (pintype "bidirectional"))
      (node (ref "JP6") (pin "2") (pinfunction "2_2") (pintype "passive"))
    )
    (net (code "96") (name "SW_MODE") (class "Default")
      (node (ref "IC1") (pin "33") (pinfunction "PA12/SPI1_SCK/I2S1_CK/USART1_RTS/CAN_TX/TIM4_CH2/TIM5_CH3_33") (pintype "bidirectional"))
      (node (ref "JP61") (pin "1") (pinfunction "1_1") (pintype "passive"))
    )
    (net (code "97") (name "SW_RANGE") (class "Default")
      (node (ref "IC1") (pin "12") (pinfunction "PA2/SPI3_MISO/I2S3_MCK/USART2_TX/TIM2_CH3/TIM5_CH3/ADC_IN2_12") (pintype "bidirectional"))
      (node (ref "JP60") (pin "1") (pinfunction "1_1") (pintype "passive"))
    )
    (net (code "98") (name "SW_SHIFT") (class "Default")
      (node (ref "IC1") (pin "2") (pinfunction "PC13/TIMESTAMP/RTC_TAMPER1_2") (pintype "bidirectional"))
      (node (ref "JP62") (pin "1") (pinfunction "1_1") (pintype "passive"))
    )
    (net (code "99") (name "TX") (class "Default")
      (node (ref "IC1") (pin "45") (pinfunction "PB8/SPI2_SCK/I2S2_CK/I2C1_SCL/USART3_TX/CAN_RX/TIM4_CH3_45") (pintype "bidirectional"))
      (node (ref "R5") (pin "2") (pinfunction "2_2") (pintype "passive"))
    )
    (net (code "100") (name "VCC") (class "Default")
      (node (ref "C24") (pin "+") (pinfunction "+_+") (pintype "passive"))
      (node (ref "C48") (pin "1") (pinfunction "1_1") (pintype "passive"))
      (node (ref "C49") (pin "1") (pinfunction "1_1") (pintype "passive"))
      (node (ref "IC8") (pin "4") (pinfunction "V+_4") (pintype "power_in"))
      (node (ref "IC9") (pin "4") (pinfunction "V+_4") (pintype "power_in"))
      (node (ref "L2") (pin "1") (pinfunction "1_1") (pintype "passive"))
    )
    (net (code "101") (name "VEE") (class "Default")
      (node (ref "C26") (pin "-") (pinfunction "-_-") (pintype "passive"))
      (node (ref "C33") (pin "2") (pinfunction "2_2") (pintype "passive"))
      (node (ref "C34") (pin "2") (pinfunction "2_2") (pintype "passive"))
      (node (ref "IC8") (pin "11") (pinfunction "V-_11") (pintype "power_in"))
      (node (ref "IC9") (pin "11") (pinfunction "V-_11") (pintype "power_in"))
      (node (ref "L4") (pin "1") (pinfunction "1_1") (pintype "passive"))
      (node (ref "R46") (pin "1") (pinfunction "1_1") (pintype "passive"))
    )
    (net (code "102") (name "VREF") (class "Default")
      (node (ref "C18") (pin "1") (pinfunction "1_1") (pintype "passive"))
      (node (ref "IC4") (pin "3") (pinfunction "VREFH_3") (pintype "bidirectional"))
      (node (ref "R14") (pin "2") (pinfunction "2_2") (pintype "passive"))
    )
    (net (code "103") (name "VREF_BIAS") (class "Default")
      (node (ref "C21") (pin "1") (pinfunction "1_1") (pintype "passive"))
      (node (ref "IC8") (pin "10") (pinfunction "+IN_10") (pintype "input"))
      (node (ref "IC8") (pin "12") (pinfunction "+IN_12") (pintype "input"))
      (node (ref "IC9") (pin "10") (pinfunction "+IN_10") (pintype "input"))
      (node (ref "IC9") (pin "12") (pinfunction "+IN_12") (pintype "input"))
      (node (ref "R14") (pin "1") (pinfunction "1_1") (pintype "passive"))
      (node (ref "R15") (pin "2") (pinfunction "2_2") (pintype "passive"))
    )
    (net (code "104") (name "unconnected-(IC1-PA15{slash}SPI1_NSS{slash}I2S1_WS{slash}SPI3_NSS{slash}I2S3_WS{slash}I2C1_SCL{slash}TIM2_CH1_ETR{slash}JTDI-Pad38)") (class "Default")
      (node (ref "IC1") (pin "38") (pinfunction "PA15/SPI1_NSS/I2S1_WS/SPI3_NSS/I2S3_WS/I2C1_SCL/TIM2_CH1_ETR/JTDI_38") (pintype "bidirectional"))
    )
    (net (code "105") (name "unconnected-(IC1-PB7{slash}I2C1_SDA{slash}USART1_RX{slash}TIM4_CH2-Pad43)") (class "Default")
      (node (ref "IC1") (pin "43") (pinfunction "PB7/I2C1_SDA/USART1_RX/TIM4_CH2_43") (pintype "bidirectional"))
    )
    (net (code "106") (name "unconnected-(IC1-PC14{slash}OSC32_IN-Pad3)") (class "Default")
      (node (ref "IC1") (pin "3") (pinfunction "PC14/OSC32_IN_3") (pintype "bidirectional"))
    )
    (net (code "107") (name "unconnected-(IC1-PC15{slash}OSC32_OUT-Pad4)") (class "Default")
      (node (ref "IC1") (pin "4") (pinfunction "PC15/OSC32_OUT_4") (pintype "bidirectional"))
    )
  )
)
